# PCB_TrafficLight.net
KiCad netlist of a schematic drawn in Altium Designer
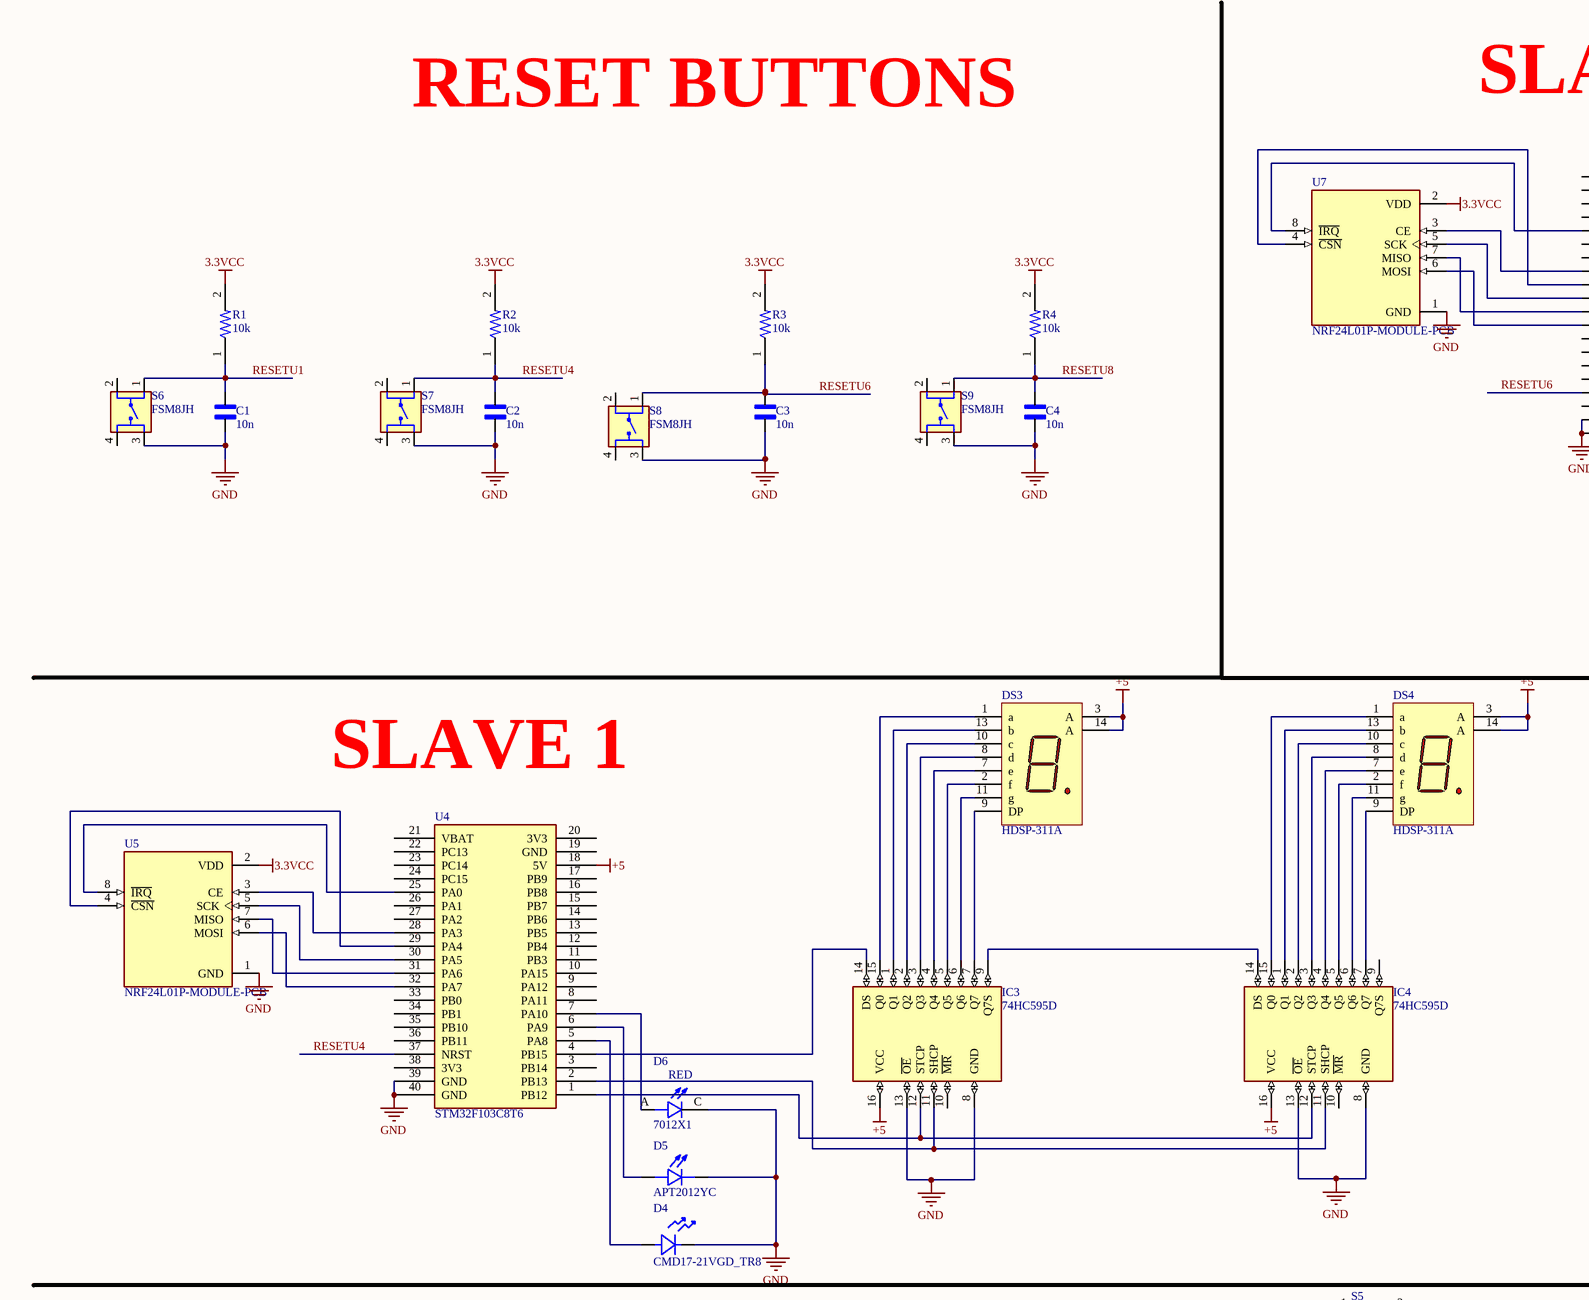
[diagram p0: PCB_TrafficLight.SchDoc, top left]
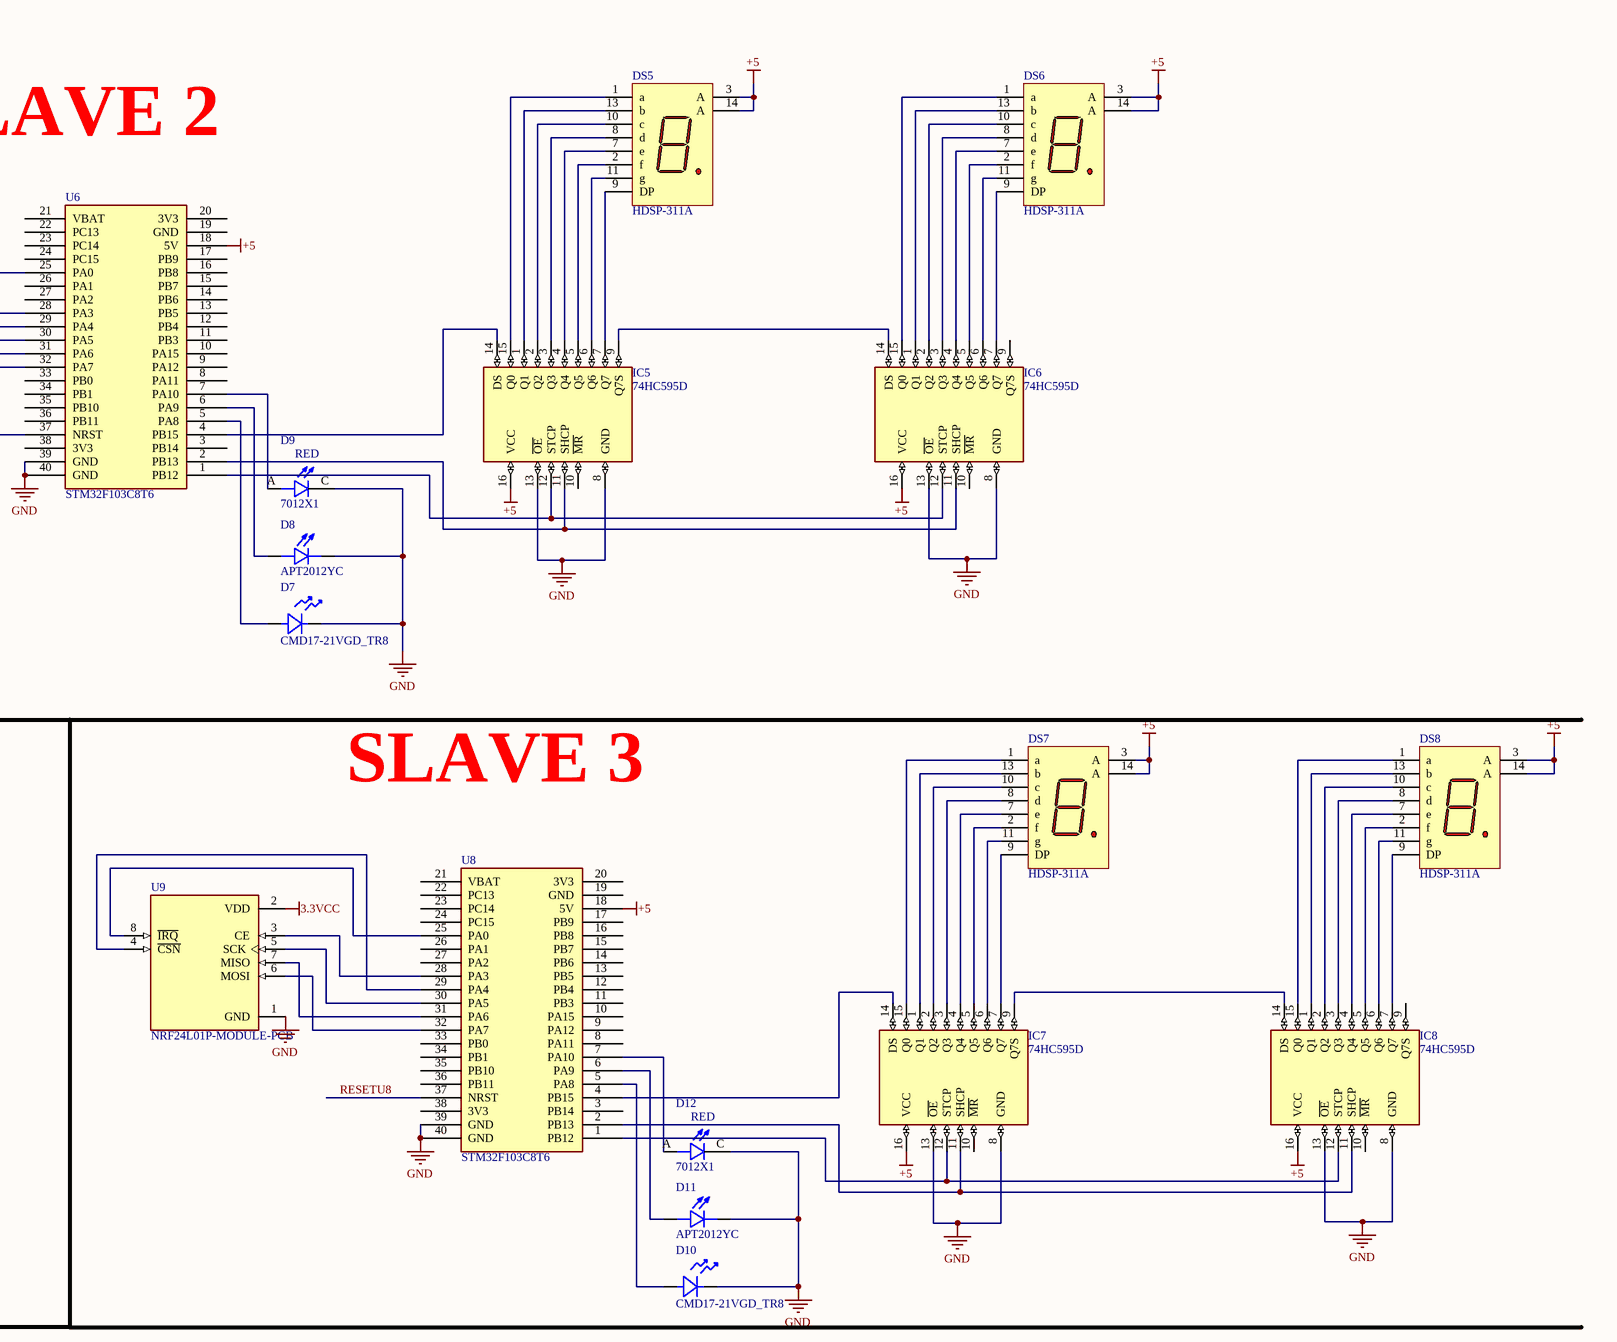
[diagram p1: PCB_TrafficLight.SchDoc, top right]
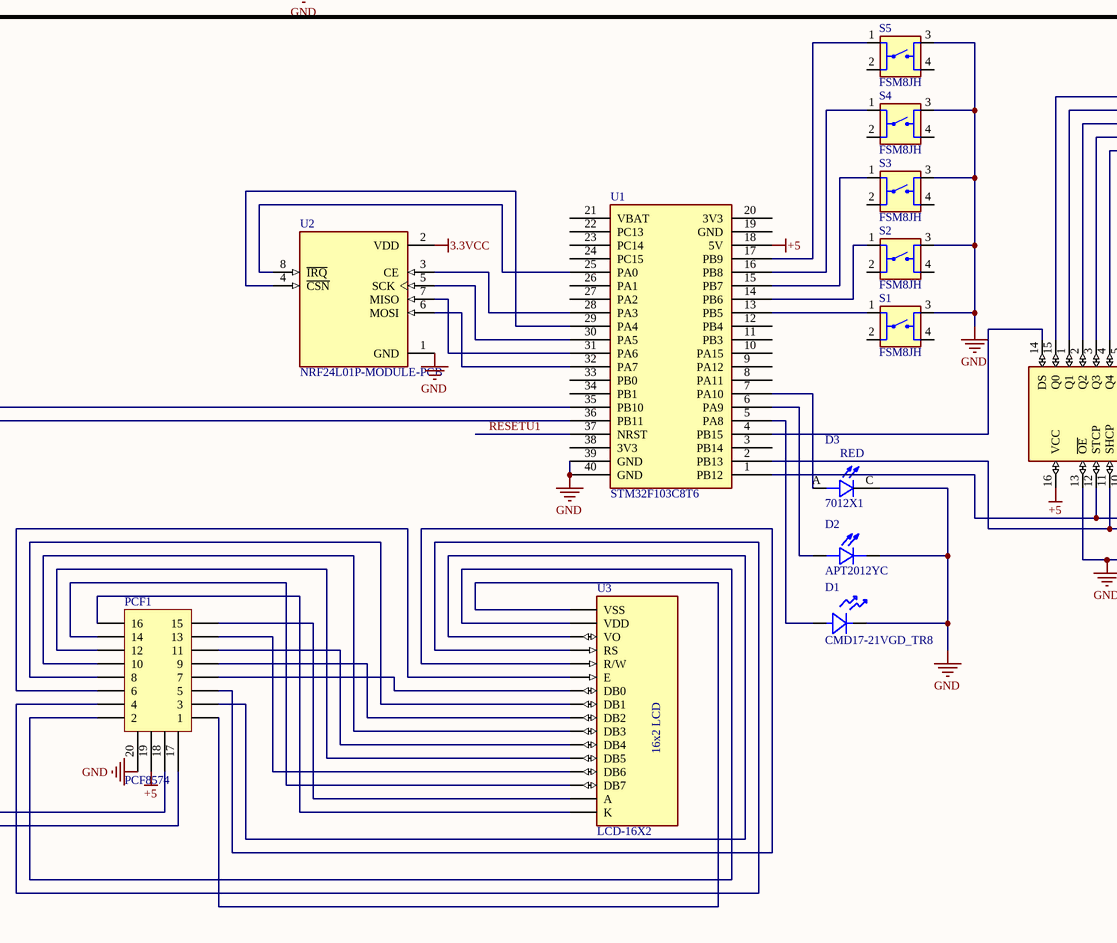
[diagram p2: PCB_TrafficLight.SchDoc, bottom left]
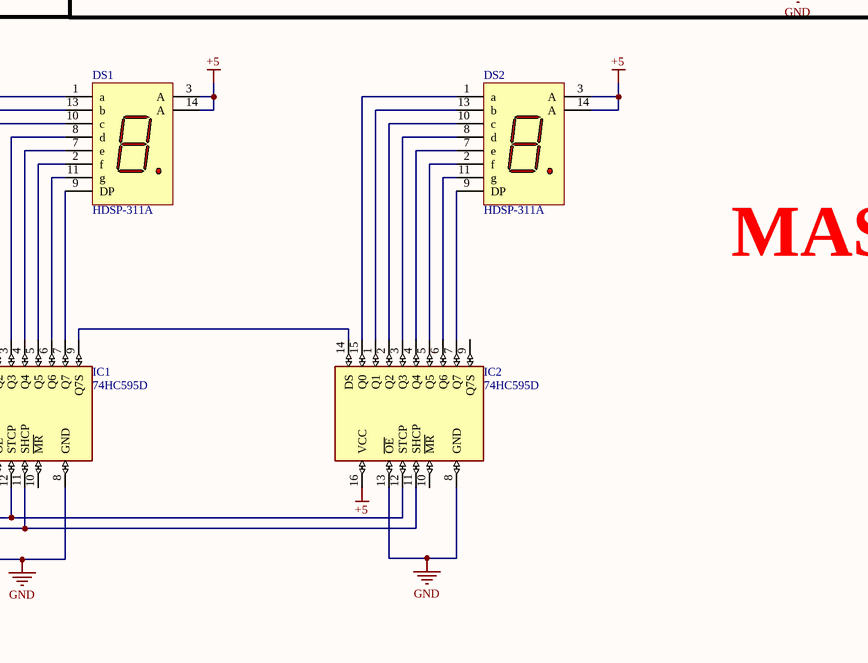
[diagram p3: PCB_TrafficLight.SchDoc, bottom right]

(export (version "E")
  (design (tool "Eeschema 10.0.6"))
  (components
    (comp (ref "C1")
      (value "10n")
      (footprint "CAPC1005X55N")
      (description "Multilayer Ceramic Capacitors MLCC - SMD/SMT")
      (fields (field (name "MF") "Murata") (field (name "MP") "GCM155R11H103KA40D"))
      (libsource (lib "GCM155R11H103KA40D") (part "GCM155R11H103KA40D"))
    )
    (comp (ref "C2")
      (value "10n")
      (footprint "CAPC1005X55N")
      (description "Multilayer Ceramic Capacitors MLCC - SMD/SMT")
      (fields (field (name "MF") "Murata") (field (name "MP") "GCM155R11H103KA40D"))
      (libsource (lib "GCM155R11H103KA40D") (part "GCM155R11H103KA40D"))
    )
    (comp (ref "C3")
      (value "10n")
      (footprint "CAPC1005X55N")
      (description "Multilayer Ceramic Capacitors MLCC - SMD/SMT")
      (fields (field (name "MF") "Murata") (field (name "MP") "GCM155R11H103KA40D"))
      (libsource (lib "GCM155R11H103KA40D") (part "GCM155R11H103KA40D"))
    )
    (comp (ref "C4")
      (value "10n")
      (footprint "CAPC1005X55N")
      (description "Multilayer Ceramic Capacitors MLCC - SMD/SMT")
      (fields (field (name "MF") "Murata") (field (name "MP") "GCM155R11H103KA40D"))
      (libsource (lib "GCM155R11H103KA40D") (part "GCM155R11H103KA40D"))
    )
    (comp (ref "D1")
      (value "CMD17-21VGD_TR8")
      (footprint "LED_CMD17-21VGD_TR8")
      (description "Green - LED Indication - Discrete 2.1V 0805 (2012 Metric)")
      (fields (field (name "MF") "VCC") (field (name "MP") "CMD17-21VGD/TR8"))
      (libsource (lib "CMD17-21VGD_TR8") (part "CMD17-21VGD_TR8"))
    )
    (comp (ref "D2")
      (value "APT2012YC")
      (footprint "LED_APT2012YC")
      (fields (field (name "MF") "{'manufacturer': u'Kingbright'}"))
      (libsource (lib "APT2012YC") (part "APT2012YC"))
    )
    (comp (ref "D3")
      (value "7012X1")
      (footprint "LED_7012X1")
      (description "Red - LED Indication - Discrete 1.7V 0805 (2012 Metric)")
      (fields (field (name "MF") "VCC"))
      (libsource (lib "7012X1") (part "7012X1"))
    )
    (comp (ref "D4")
      (value "CMD17-21VGD_TR8")
      (footprint "LED_CMD17-21VGD_TR8")
      (description "Green - LED Indication - Discrete 2.1V 0805 (2012 Metric)")
      (fields (field (name "MF") "VCC") (field (name "MP") "CMD17-21VGD/TR8"))
      (libsource (lib "CMD17-21VGD_TR8") (part "CMD17-21VGD_TR8"))
    )
    (comp (ref "D5")
      (value "APT2012YC")
      (footprint "LED_APT2012YC")
      (fields (field (name "MF") "{'manufacturer': u'Kingbright'}"))
      (libsource (lib "APT2012YC") (part "APT2012YC"))
    )
    (comp (ref "D6")
      (value "7012X1")
      (footprint "LED_7012X1")
      (description "Red - LED Indication - Discrete 1.7V 0805 (2012 Metric)")
      (fields (field (name "MF") "VCC"))
      (libsource (lib "7012X1") (part "7012X1"))
    )
    (comp (ref "D7")
      (value "CMD17-21VGD_TR8")
      (footprint "LED_CMD17-21VGD_TR8")
      (description "Green - LED Indication - Discrete 2.1V 0805 (2012 Metric)")
      (fields (field (name "MF") "VCC") (field (name "MP") "CMD17-21VGD/TR8"))
      (libsource (lib "CMD17-21VGD_TR8") (part "CMD17-21VGD_TR8"))
    )
    (comp (ref "D8")
      (value "APT2012YC")
      (footprint "LED_APT2012YC")
      (fields (field (name "MF") "{'manufacturer': u'Kingbright'}"))
      (libsource (lib "APT2012YC") (part "APT2012YC"))
    )
    (comp (ref "D9")
      (value "7012X1")
      (footprint "LED_7012X1")
      (description "Red - LED Indication - Discrete 1.7V 0805 (2012 Metric)")
      (fields (field (name "MF") "VCC"))
      (libsource (lib "7012X1") (part "7012X1"))
    )
    (comp (ref "D10")
      (value "CMD17-21VGD_TR8")
      (footprint "LED_CMD17-21VGD_TR8")
      (description "Green - LED Indication - Discrete 2.1V 0805 (2012 Metric)")
      (fields (field (name "MF") "VCC") (field (name "MP") "CMD17-21VGD/TR8"))
      (libsource (lib "CMD17-21VGD_TR8") (part "CMD17-21VGD_TR8"))
    )
    (comp (ref "D11")
      (value "APT2012YC")
      (footprint "LED_APT2012YC")
      (fields (field (name "MF") "{'manufacturer': u'Kingbright'}"))
      (libsource (lib "APT2012YC") (part "APT2012YC"))
    )
    (comp (ref "D12")
      (value "7012X1")
      (footprint "LED_7012X1")
      (description "Red - LED Indication - Discrete 1.7V 0805 (2012 Metric)")
      (fields (field (name "MF") "VCC"))
      (libsource (lib "7012X1") (part "7012X1"))
    )
    (comp (ref "DS1")
      (value "HDSP-311A")
      (footprint "F-10(14)")
      (description "10.16 mm Single Digit General Purpose AlGaAs Red 7-Segment Display: CA, RH DP")
      (fields (field (name "PUBLISHER") "Altium Limited"))
      (libsource (lib "Agilent LED Display 7-Segment, 1-Digit") (part "HDSP-311A"))
    )
    (comp (ref "DS2")
      (value "HDSP-311A")
      (footprint "F-10(14)")
      (description "10.16 mm Single Digit General Purpose AlGaAs Red 7-Segment Display: CA, RH DP")
      (fields (field (name "PUBLISHER") "Altium Limited"))
      (libsource (lib "Agilent LED Display 7-Segment, 1-Digit") (part "HDSP-311A"))
    )
    (comp (ref "DS3")
      (value "HDSP-311A")
      (footprint "F-10(14)")
      (description "10.16 mm Single Digit General Purpose AlGaAs Red 7-Segment Display: CA, RH DP")
      (fields (field (name "PUBLISHER") "Altium Limited"))
      (libsource (lib "Agilent LED Display 7-Segment, 1-Digit") (part "HDSP-311A"))
    )
    (comp (ref "DS4")
      (value "HDSP-311A")
      (footprint "F-10(14)")
      (description "10.16 mm Single Digit General Purpose AlGaAs Red 7-Segment Display: CA, RH DP")
      (fields (field (name "PUBLISHER") "Altium Limited"))
      (libsource (lib "Agilent LED Display 7-Segment, 1-Digit") (part "HDSP-311A"))
    )
    (comp (ref "DS5")
      (value "HDSP-311A")
      (footprint "F-10(14)")
      (description "10.16 mm Single Digit General Purpose AlGaAs Red 7-Segment Display: CA, RH DP")
      (fields (field (name "PUBLISHER") "Altium Limited"))
      (libsource (lib "Agilent LED Display 7-Segment, 1-Digit") (part "HDSP-311A"))
    )
    (comp (ref "DS6")
      (value "HDSP-311A")
      (footprint "F-10(14)")
      (description "10.16 mm Single Digit General Purpose AlGaAs Red 7-Segment Display: CA, RH DP")
      (fields (field (name "PUBLISHER") "Altium Limited"))
      (libsource (lib "Agilent LED Display 7-Segment, 1-Digit") (part "HDSP-311A"))
    )
    (comp (ref "DS7")
      (value "HDSP-311A")
      (footprint "F-10(14)")
      (description "10.16 mm Single Digit General Purpose AlGaAs Red 7-Segment Display: CA, RH DP")
      (fields (field (name "PUBLISHER") "Altium Limited"))
      (libsource (lib "Agilent LED Display 7-Segment, 1-Digit") (part "HDSP-311A"))
    )
    (comp (ref "DS8")
      (value "HDSP-311A")
      (footprint "F-10(14)")
      (description "10.16 mm Single Digit General Purpose AlGaAs Red 7-Segment Display: CA, RH DP")
      (fields (field (name "PUBLISHER") "Altium Limited"))
      (libsource (lib "Agilent LED Display 7-Segment, 1-Digit") (part "HDSP-311A"))
    )
    (comp (ref "IC1")
      (value "74HC595D")
      (footprint "SOIC127P600X175-16N")
      (description "Shift Register Single 8-Bit Serial to Serial/Parallel 16-Pin SOIC T/R")
      (fields (field (name "MF") "NXP Semiconductors"))
      (libsource (lib "74HC595D") (part "74HC595D"))
    )
    (comp (ref "IC2")
      (value "74HC595D")
      (footprint "SOIC127P600X175-16N")
      (description "Shift Register Single 8-Bit Serial to Serial/Parallel 16-Pin SOIC T/R")
      (fields (field (name "MF") "NXP Semiconductors"))
      (libsource (lib "74HC595D") (part "74HC595D"))
    )
    (comp (ref "IC3")
      (value "74HC595D")
      (footprint "SOIC127P600X175-16N")
      (description "Shift Register Single 8-Bit Serial to Serial/Parallel 16-Pin SOIC T/R")
      (fields (field (name "MF") "NXP Semiconductors"))
      (libsource (lib "74HC595D") (part "74HC595D"))
    )
    (comp (ref "IC4")
      (value "74HC595D")
      (footprint "SOIC127P600X175-16N")
      (description "Shift Register Single 8-Bit Serial to Serial/Parallel 16-Pin SOIC T/R")
      (fields (field (name "MF") "NXP Semiconductors"))
      (libsource (lib "74HC595D") (part "74HC595D"))
    )
    (comp (ref "IC5")
      (value "74HC595D")
      (footprint "SOIC127P600X175-16N")
      (description "Shift Register Single 8-Bit Serial to Serial/Parallel 16-Pin SOIC T/R")
      (fields (field (name "MF") "NXP Semiconductors"))
      (libsource (lib "74HC595D") (part "74HC595D"))
    )
    (comp (ref "IC6")
      (value "74HC595D")
      (footprint "SOIC127P600X175-16N")
      (description "Shift Register Single 8-Bit Serial to Serial/Parallel 16-Pin SOIC T/R")
      (fields (field (name "MF") "NXP Semiconductors"))
      (libsource (lib "74HC595D") (part "74HC595D"))
    )
    (comp (ref "IC7")
      (value "74HC595D")
      (footprint "SOIC127P600X175-16N")
      (description "Shift Register Single 8-Bit Serial to Serial/Parallel 16-Pin SOIC T/R")
      (fields (field (name "MF") "NXP Semiconductors"))
      (libsource (lib "74HC595D") (part "74HC595D"))
    )
    (comp (ref "IC8")
      (value "74HC595D")
      (footprint "SOIC127P600X175-16N")
      (description "Shift Register Single 8-Bit Serial to Serial/Parallel 16-Pin SOIC T/R")
      (fields (field (name "MF") "NXP Semiconductors"))
      (libsource (lib "74HC595D") (part "74HC595D"))
    )
    (comp (ref "PCF1") (value "PCF8574") (footprint "PCF8574") (libsource (lib "PCF8574") (part "PCF8574")))
    (comp (ref "R1")
      (value "10k")
      (footprint "RESC1608X50N_CPF0603F10KC1")
      (description "Res Thin Film 0603 10K Ohm 1% 1/16W Â±50ppm/Â°C Molded SMD SMD Paper T/R")
      (fields (field (name "TOLERANCE") "1%") (field (name "MF") "TE Connectivity"))
      (libsource (lib "CPF0603F10KC1") (part "CPF0603F10KC1"))
    )
    (comp (ref "R2")
      (value "10k")
      (footprint "RESC1608X50N_CPF0603F10KC1")
      (description "Res Thin Film 0603 10K Ohm 1% 1/16W Â±50ppm/Â°C Molded SMD SMD Paper T/R")
      (fields (field (name "TOLERANCE") "1%") (field (name "MF") "TE Connectivity"))
      (libsource (lib "CPF0603F10KC1") (part "CPF0603F10KC1"))
    )
    (comp (ref "R3")
      (value "10k")
      (footprint "RESC1608X50N_CPF0603F10KC1")
      (description "Res Thin Film 0603 10K Ohm 1% 1/16W Â±50ppm/Â°C Molded SMD SMD Paper T/R")
      (fields (field (name "TOLERANCE") "1%") (field (name "MF") "TE Connectivity"))
      (libsource (lib "CPF0603F10KC1") (part "CPF0603F10KC1"))
    )
    (comp (ref "R4")
      (value "10k")
      (footprint "RESC1608X50N_CPF0603F10KC1")
      (description "Res Thin Film 0603 10K Ohm 1% 1/16W Â±50ppm/Â°C Molded SMD SMD Paper T/R")
      (fields (field (name "TOLERANCE") "1%") (field (name "MF") "TE Connectivity"))
      (libsource (lib "CPF0603F10KC1") (part "CPF0603F10KC1"))
    )
    (comp (ref "S1")
      (value "FSM8JH")
      (footprint "SW_FSM8JH")
      (description "Tactile Switch SPST-NO Top Actuated Through Hole")
      (fields (field (name "MF") "TE Connectivity"))
      (libsource (lib "FSM8JH") (part "FSM8JH"))
    )
    (comp (ref "S2")
      (value "FSM8JH")
      (footprint "SW_FSM8JH")
      (description "Tactile Switch SPST-NO Top Actuated Through Hole")
      (fields (field (name "MF") "TE Connectivity"))
      (libsource (lib "FSM8JH") (part "FSM8JH"))
    )
    (comp (ref "S3")
      (value "FSM8JH")
      (footprint "SW_FSM8JH")
      (description "Tactile Switch SPST-NO Top Actuated Through Hole")
      (fields (field (name "MF") "TE Connectivity"))
      (libsource (lib "FSM8JH") (part "FSM8JH"))
    )
    (comp (ref "S4")
      (value "FSM8JH")
      (footprint "SW_FSM8JH")
      (description "Tactile Switch SPST-NO Top Actuated Through Hole")
      (fields (field (name "MF") "TE Connectivity"))
      (libsource (lib "FSM8JH") (part "FSM8JH"))
    )
    (comp (ref "S5")
      (value "FSM8JH")
      (footprint "SW_FSM8JH")
      (description "Tactile Switch SPST-NO Top Actuated Through Hole")
      (fields (field (name "MF") "TE Connectivity"))
      (libsource (lib "FSM8JH") (part "FSM8JH"))
    )
    (comp (ref "S6")
      (value "FSM8JH")
      (footprint "SW_FSM8JH")
      (description "Tactile Switch SPST-NO Top Actuated Through Hole")
      (fields (field (name "MF") "TE Connectivity"))
      (libsource (lib "") (part "FSM8JH_1"))
    )
    (comp (ref "S7")
      (value "FSM8JH")
      (footprint "SW_FSM8JH")
      (description "Tactile Switch SPST-NO Top Actuated Through Hole")
      (fields (field (name "MF") "TE Connectivity"))
      (libsource (lib "") (part "FSM8JH_1"))
    )
    (comp (ref "S8")
      (value "FSM8JH")
      (footprint "SW_FSM8JH")
      (description "Tactile Switch SPST-NO Top Actuated Through Hole")
      (fields (field (name "MF") "TE Connectivity"))
      (libsource (lib "") (part "FSM8JH_1"))
    )
    (comp (ref "S9")
      (value "FSM8JH")
      (footprint "SW_FSM8JH")
      (description "Tactile Switch SPST-NO Top Actuated Through Hole")
      (fields (field (name "MF") "TE Connectivity"))
      (libsource (lib "") (part "FSM8JH_1"))
    )
    (comp (ref "U1")
      (value "STM32F103C8T6")
      (footprint "Stm32 BluePill")
      (description "Designed By @Alixahedi")
      (libsource (lib "Stm32 Blue Pill") (part "BluePill"))
    )
    (comp (ref "U2")
      (value "NRF24L01P-MODULE-PCB")
      (footprint "XCVR_NRF24L01P-MODULE-PCB")
      (description "- Transceiver For Use With nRF24L01+")
      (fields (field (name "MF") "Nordic Semiconductor"))
      (libsource (lib "NRF24L01P-MODULE-PCB") (part "NRF24L01P-MODULE-PCB"))
    )
    (comp (ref "U3")
      (value "LCD-16X2")
      (footprint "MODULE_LCD-16X2")
      (description "Display Development Tools 16x2 Black on Green Char LCD w Backlight")
      (fields (field (name "MF") "Gravitech"))
      (libsource (lib "LCD-16X2") (part "LCD-16X2"))
    )
    (comp (ref "U4")
      (value "STM32F103C8T6")
      (footprint "Stm32 BluePill")
      (description "Designed By @Alixahedi")
      (libsource (lib "Stm32 Blue Pill") (part "BluePill"))
    )
    (comp (ref "U5")
      (value "NRF24L01P-MODULE-PCB")
      (footprint "XCVR_NRF24L01P-MODULE-PCB")
      (description "- Transceiver For Use With nRF24L01+")
      (fields (field (name "MF") "Nordic Semiconductor"))
      (libsource (lib "NRF24L01P-MODULE-PCB") (part "NRF24L01P-MODULE-PCB"))
    )
    (comp (ref "U6")
      (value "STM32F103C8T6")
      (footprint "Stm32 BluePill")
      (description "Designed By @Alixahedi")
      (libsource (lib "Stm32 Blue Pill") (part "BluePill"))
    )
    (comp (ref "U7")
      (value "NRF24L01P-MODULE-PCB")
      (footprint "XCVR_NRF24L01P-MODULE-PCB")
      (description "- Transceiver For Use With nRF24L01+")
      (fields (field (name "MF") "Nordic Semiconductor"))
      (libsource (lib "NRF24L01P-MODULE-PCB") (part "NRF24L01P-MODULE-PCB"))
    )
    (comp (ref "U8")
      (value "STM32F103C8T6")
      (footprint "Stm32 BluePill")
      (description "Designed By @Alixahedi")
      (libsource (lib "Stm32 Blue Pill") (part "BluePill"))
    )
    (comp (ref "U9")
      (value "NRF24L01P-MODULE-PCB")
      (footprint "XCVR_NRF24L01P-MODULE-PCB")
      (description "- Transceiver For Use With nRF24L01+")
      (fields (field (name "MF") "Nordic Semiconductor"))
      (libsource (lib "NRF24L01P-MODULE-PCB") (part "NRF24L01P-MODULE-PCB"))
    )
  )
  (nets
    (net (code "1") (name "+5") (class "Default")
      (node (ref "DS1") (pin "14") (pinfunction "A_14") (pintype "passive"))
      (node (ref "DS1") (pin "3") (pinfunction "A_3") (pintype "passive"))
      (node (ref "DS2") (pin "14") (pinfunction "A_14") (pintype "passive"))
      (node (ref "DS2") (pin "3") (pinfunction "A_3") (pintype "passive"))
      (node (ref "DS3") (pin "14") (pinfunction "A_14") (pintype "passive"))
      (node (ref "DS3") (pin "3") (pinfunction "A_3") (pintype "passive"))
      (node (ref "DS4") (pin "14") (pinfunction "A_14") (pintype "passive"))
      (node (ref "DS4") (pin "3") (pinfunction "A_3") (pintype "passive"))
      (node (ref "DS5") (pin "14") (pinfunction "A_14") (pintype "passive"))
      (node (ref "DS5") (pin "3") (pinfunction "A_3") (pintype "passive"))
      (node (ref "DS6") (pin "14") (pinfunction "A_14") (pintype "passive"))
      (node (ref "DS6") (pin "3") (pinfunction "A_3") (pintype "passive"))
      (node (ref "DS7") (pin "14") (pinfunction "A_14") (pintype "passive"))
      (node (ref "DS7") (pin "3") (pinfunction "A_3") (pintype "passive"))
      (node (ref "DS8") (pin "14") (pinfunction "A_14") (pintype "passive"))
      (node (ref "DS8") (pin "3") (pinfunction "A_3") (pintype "passive"))
      (node (ref "IC1") (pin "16") (pinfunction "VCC_16") (pintype "bidirectional"))
      (node (ref "IC2") (pin "16") (pinfunction "VCC_16") (pintype "bidirectional"))
      (node (ref "IC3") (pin "16") (pinfunction "VCC_16") (pintype "bidirectional"))
      (node (ref "IC4") (pin "16") (pinfunction "VCC_16") (pintype "bidirectional"))
      (node (ref "IC5") (pin "16") (pinfunction "VCC_16") (pintype "bidirectional"))
      (node (ref "IC6") (pin "16") (pinfunction "VCC_16") (pintype "bidirectional"))
      (node (ref "IC7") (pin "16") (pinfunction "VCC_16") (pintype "bidirectional"))
      (node (ref "IC8") (pin "16") (pinfunction "VCC_16") (pintype "bidirectional"))
      (node (ref "PCF1") (pin "19") (pinfunction "19_19") (pintype "passive"))
      (node (ref "U1") (pin "18") (pinfunction "5V_18") (pintype "passive"))
      (node (ref "U4") (pin "18") (pinfunction "5V_18") (pintype "passive"))
      (node (ref "U6") (pin "18") (pinfunction "5V_18") (pintype "passive"))
      (node (ref "U8") (pin "18") (pinfunction "5V_18") (pintype "passive"))
    )
    (net (code "2") (name "/RESETU1") (class "Default")
      (node (ref "C1") (pin "2") (pinfunction "2_2") (pintype "passive"))
      (node (ref "R1") (pin "1") (pinfunction "1_1") (pintype "passive"))
      (node (ref "S6") (pin "1") (pinfunction "1_1") (pintype "passive"))
      (node (ref "U1") (pin "37") (pinfunction "NRST_37") (pintype "passive"))
    )
    (net (code "3") (name "/RESETU4") (class "Default")
      (node (ref "C2") (pin "2") (pinfunction "2_2") (pintype "passive"))
      (node (ref "R2") (pin "1") (pinfunction "1_1") (pintype "passive"))
      (node (ref "S7") (pin "1") (pinfunction "1_1") (pintype "passive"))
      (node (ref "U4") (pin "37") (pinfunction "NRST_37") (pintype "passive"))
    )
    (net (code "4") (name "/RESETU6") (class "Default")
      (node (ref "C3") (pin "2") (pinfunction "2_2") (pintype "passive"))
      (node (ref "R3") (pin "1") (pinfunction "1_1") (pintype "passive"))
      (node (ref "S8") (pin "1") (pinfunction "1_1") (pintype "passive"))
      (node (ref "U6") (pin "37") (pinfunction "NRST_37") (pintype "passive"))
    )
    (net (code "5") (name "/RESETU8") (class "Default")
      (node (ref "C4") (pin "2") (pinfunction "2_2") (pintype "passive"))
      (node (ref "R4") (pin "1") (pinfunction "1_1") (pintype "passive"))
      (node (ref "S9") (pin "1") (pinfunction "1_1") (pintype "passive"))
      (node (ref "U8") (pin "37") (pinfunction "NRST_37") (pintype "passive"))
    )
    (net (code "6") (name "3.3VCC") (class "Default")
      (node (ref "R1") (pin "2") (pinfunction "2_2") (pintype "passive"))
      (node (ref "R2") (pin "2") (pinfunction "2_2") (pintype "passive"))
      (node (ref "R3") (pin "2") (pinfunction "2_2") (pintype "passive"))
      (node (ref "R4") (pin "2") (pinfunction "2_2") (pintype "passive"))
      (node (ref "U2") (pin "2") (pinfunction "VDD_2") (pintype "power_in"))
      (node (ref "U5") (pin "2") (pinfunction "VDD_2") (pintype "power_in"))
      (node (ref "U7") (pin "2") (pinfunction "VDD_2") (pintype "power_in"))
      (node (ref "U9") (pin "2") (pinfunction "VDD_2") (pintype "power_in"))
    )
    (net (code "7") (name "GND") (class "Default")
      (node (ref "C1") (pin "1") (pinfunction "1_1") (pintype "passive"))
      (node (ref "C2") (pin "1") (pinfunction "1_1") (pintype "passive"))
      (node (ref "C3") (pin "1") (pinfunction "1_1") (pintype "passive"))
      (node (ref "C4") (pin "1") (pinfunction "1_1") (pintype "passive"))
      (node (ref "D1") (pin "2") (pinfunction "2_2") (pintype "passive"))
      (node (ref "D10") (pin "2") (pinfunction "2_2") (pintype "passive"))
      (node (ref "D11") (pin "1") (pinfunction "C_1") (pintype "passive"))
      (node (ref "D12") (pin "C") (pinfunction "C_C") (pintype "passive"))
      (node (ref "D2") (pin "1") (pinfunction "C_1") (pintype "passive"))
      (node (ref "D3") (pin "C") (pinfunction "C_C") (pintype "passive"))
      (node (ref "D4") (pin "2") (pinfunction "2_2") (pintype "passive"))
      (node (ref "D5") (pin "1") (pinfunction "C_1") (pintype "passive"))
      (node (ref "D6") (pin "C") (pinfunction "C_C") (pintype "passive"))
      (node (ref "D7") (pin "2") (pinfunction "2_2") (pintype "passive"))
      (node (ref "D8") (pin "1") (pinfunction "C_1") (pintype "passive"))
      (node (ref "D9") (pin "C") (pinfunction "C_C") (pintype "passive"))
      (node (ref "IC1") (pin "13") (pinfunction "~{OE}_13") (pintype "bidirectional"))
      (node (ref "IC1") (pin "8") (pinfunction "GND_8") (pintype "bidirectional"))
      (node (ref "IC2") (pin "13") (pinfunction "~{OE}_13") (pintype "bidirectional"))
      (node (ref "IC2") (pin "8") (pinfunction "GND_8") (pintype "bidirectional"))
      (node (ref "IC3") (pin "13") (pinfunction "~{OE}_13") (pintype "bidirectional"))
      (node (ref "IC3") (pin "8") (pinfunction "GND_8") (pintype "bidirectional"))
      (node (ref "IC4") (pin "13") (pinfunction "~{OE}_13") (pintype "bidirectional"))
      (node (ref "IC4") (pin "8") (pinfunction "GND_8") (pintype "bidirectional"))
      (node (ref "IC5") (pin "13") (pinfunction "~{OE}_13") (pintype "bidirectional"))
      (node (ref "IC5") (pin "8") (pinfunction "GND_8") (pintype "bidirectional"))
      (node (ref "IC6") (pin "13") (pinfunction "~{OE}_13") (pintype "bidirectional"))
      (node (ref "IC6") (pin "8") (pinfunction "GND_8") (pintype "bidirectional"))
      (node (ref "IC7") (pin "13") (pinfunction "~{OE}_13") (pintype "bidirectional"))
      (node (ref "IC7") (pin "8") (pinfunction "GND_8") (pintype "bidirectional"))
      (node (ref "IC8") (pin "13") (pinfunction "~{OE}_13") (pintype "bidirectional"))
      (node (ref "IC8") (pin "8") (pinfunction "GND_8") (pintype "bidirectional"))
      (node (ref "PCF1") (pin "20") (pinfunction "20_20") (pintype "passive"))
      (node (ref "S1") (pin "3") (pinfunction "3_3") (pintype "passive"))
      (node (ref "S2") (pin "3") (pinfunction "3_3") (pintype "passive"))
      (node (ref "S3") (pin "3") (pinfunction "3_3") (pintype "passive"))
      (node (ref "S4") (pin "3") (pinfunction "3_3") (pintype "passive"))
      (node (ref "S5") (pin "3") (pinfunction "3_3") (pintype "passive"))
      (node (ref "S6") (pin "3") (pinfunction "3_3") (pintype "passive"))
      (node (ref "S7") (pin "3") (pinfunction "3_3") (pintype "passive"))
      (node (ref "S8") (pin "3") (pinfunction "3_3") (pintype "passive"))
      (node (ref "S9") (pin "3") (pinfunction "3_3") (pintype "passive"))
      (node (ref "U1") (pin "39") (pinfunction "GND_39") (pintype "passive"))
      (node (ref "U1") (pin "40") (pinfunction "GND_40") (pintype "passive"))
      (node (ref "U2") (pin "1") (pinfunction "GND_1") (pintype "power_in"))
      (node (ref "U4") (pin "39") (pinfunction "GND_39") (pintype "passive"))
      (node (ref "U4") (pin "40") (pinfunction "GND_40") (pintype "passive"))
      (node (ref "U5") (pin "1") (pinfunction "GND_1") (pintype "power_in"))
      (node (ref "U6") (pin "39") (pinfunction "GND_39") (pintype "passive"))
      (node (ref "U6") (pin "40") (pinfunction "GND_40") (pintype "passive"))
      (node (ref "U7") (pin "1") (pinfunction "GND_1") (pintype "power_in"))
      (node (ref "U8") (pin "39") (pinfunction "GND_39") (pintype "passive"))
      (node (ref "U8") (pin "40") (pinfunction "GND_40") (pintype "passive"))
      (node (ref "U9") (pin "1") (pinfunction "GND_1") (pintype "power_in"))
    )
    (net (code "8") (name "Net-(D2-A)") (class "Default")
      (node (ref "D2") (pin "2") (pinfunction "A_2") (pintype "passive"))
      (node (ref "U1") (pin "6") (pinfunction "PA9_6") (pintype "passive"))
    )
    (net (code "9") (name "Net-(D5-A)") (class "Default")
      (node (ref "D5") (pin "2") (pinfunction "A_2") (pintype "passive"))
      (node (ref "U4") (pin "6") (pinfunction "PA9_6") (pintype "passive"))
    )
    (net (code "10") (name "Net-(D8-A)") (class "Default")
      (node (ref "D8") (pin "2") (pinfunction "A_2") (pintype "passive"))
      (node (ref "U6") (pin "6") (pinfunction "PA9_6") (pintype "passive"))
    )
    (net (code "11") (name "Net-(D11-A)") (class "Default")
      (node (ref "D11") (pin "2") (pinfunction "A_2") (pintype "passive"))
      (node (ref "U8") (pin "6") (pinfunction "PA9_6") (pintype "passive"))
    )
    (net (code "12") (name "Net-(DS1-DP)") (class "Default")
      (node (ref "DS1") (pin "9") (pinfunction "DP_9") (pintype "passive"))
      (node (ref "IC1") (pin "7") (pinfunction "Q7_7") (pintype "bidirectional"))
    )
    (net (code "13") (name "Net-(DS1-a)") (class "Default")
      (node (ref "DS1") (pin "1") (pinfunction "a_1") (pintype "passive"))
      (node (ref "IC1") (pin "15") (pinfunction "Q0_15") (pintype "bidirectional"))
    )
    (net (code "14") (name "Net-(DS1-b)") (class "Default")
      (node (ref "DS1") (pin "13") (pinfunction "b_13") (pintype "passive"))
      (node (ref "IC1") (pin "1") (pinfunction "Q1_1") (pintype "bidirectional"))
    )
    (net (code "15") (name "Net-(DS1-c)") (class "Default")
      (node (ref "DS1") (pin "10") (pinfunction "c_10") (pintype "passive"))
      (node (ref "IC1") (pin "2") (pinfunction "Q2_2") (pintype "bidirectional"))
    )
    (net (code "16") (name "Net-(DS1-d)") (class "Default")
      (node (ref "DS1") (pin "8") (pinfunction "d_8") (pintype "passive"))
      (node (ref "IC1") (pin "3") (pinfunction "Q3_3") (pintype "bidirectional"))
    )
    (net (code "17") (name "Net-(DS1-e)") (class "Default")
      (node (ref "DS1") (pin "7") (pinfunction "e_7") (pintype "passive"))
      (node (ref "IC1") (pin "4") (pinfunction "Q4_4") (pintype "bidirectional"))
    )
    (net (code "18") (name "Net-(DS1-f)") (class "Default")
      (node (ref "DS1") (pin "2") (pinfunction "f_2") (pintype "passive"))
      (node (ref "IC1") (pin "5") (pinfunction "Q5_5") (pintype "bidirectional"))
    )
    (net (code "19") (name "Net-(DS1-g)") (class "Default")
      (node (ref "DS1") (pin "11") (pinfunction "g_11") (pintype "passive"))
      (node (ref "IC1") (pin "6") (pinfunction "Q6_6") (pintype "bidirectional"))
    )
    (net (code "20") (name "Net-(DS2-DP)") (class "Default")
      (node (ref "DS2") (pin "9") (pinfunction "DP_9") (pintype "passive"))
      (node (ref "IC2") (pin "7") (pinfunction "Q7_7") (pintype "bidirectional"))
    )
    (net (code "21") (name "Net-(DS2-a)") (class "Default")
      (node (ref "DS2") (pin "1") (pinfunction "a_1") (pintype "passive"))
      (node (ref "IC2") (pin "15") (pinfunction "Q0_15") (pintype "bidirectional"))
    )
    (net (code "22") (name "Net-(DS2-b)") (class "Default")
      (node (ref "DS2") (pin "13") (pinfunction "b_13") (pintype "passive"))
      (node (ref "IC2") (pin "1") (pinfunction "Q1_1") (pintype "bidirectional"))
    )
    (net (code "23") (name "Net-(DS2-c)") (class "Default")
      (node (ref "DS2") (pin "10") (pinfunction "c_10") (pintype "passive"))
      (node (ref "IC2") (pin "2") (pinfunction "Q2_2") (pintype "bidirectional"))
    )
    (net (code "24") (name "Net-(DS2-d)") (class "Default")
      (node (ref "DS2") (pin "8") (pinfunction "d_8") (pintype "passive"))
      (node (ref "IC2") (pin "3") (pinfunction "Q3_3") (pintype "bidirectional"))
    )
    (net (code "25") (name "Net-(DS2-e)") (class "Default")
      (node (ref "DS2") (pin "7") (pinfunction "e_7") (pintype "passive"))
      (node (ref "IC2") (pin "4") (pinfunction "Q4_4") (pintype "bidirectional"))
    )
    (net (code "26") (name "Net-(DS2-f)") (class "Default")
      (node (ref "DS2") (pin "2") (pinfunction "f_2") (pintype "passive"))
      (node (ref "IC2") (pin "5") (pinfunction "Q5_5") (pintype "bidirectional"))
    )
    (net (code "27") (name "Net-(DS2-g)") (class "Default")
      (node (ref "DS2") (pin "11") (pinfunction "g_11") (pintype "passive"))
      (node (ref "IC2") (pin "6") (pinfunction "Q6_6") (pintype "bidirectional"))
    )
    (net (code "28") (name "Net-(DS3-DP)") (class "Default")
      (node (ref "DS3") (pin "9") (pinfunction "DP_9") (pintype "passive"))
      (node (ref "IC3") (pin "7") (pinfunction "Q7_7") (pintype "bidirectional"))
    )
    (net (code "29") (name "Net-(DS3-a)") (class "Default")
      (node (ref "DS3") (pin "1") (pinfunction "a_1") (pintype "passive"))
      (node (ref "IC3") (pin "15") (pinfunction "Q0_15") (pintype "bidirectional"))
    )
    (net (code "30") (name "Net-(DS3-b)") (class "Default")
      (node (ref "DS3") (pin "13") (pinfunction "b_13") (pintype "passive"))
      (node (ref "IC3") (pin "1") (pinfunction "Q1_1") (pintype "bidirectional"))
    )
    (net (code "31") (name "Net-(DS3-c)") (class "Default")
      (node (ref "DS3") (pin "10") (pinfunction "c_10") (pintype "passive"))
      (node (ref "IC3") (pin "2") (pinfunction "Q2_2") (pintype "bidirectional"))
    )
    (net (code "32") (name "Net-(DS3-d)") (class "Default")
      (node (ref "DS3") (pin "8") (pinfunction "d_8") (pintype "passive"))
      (node (ref "IC3") (pin "3") (pinfunction "Q3_3") (pintype "bidirectional"))
    )
    (net (code "33") (name "Net-(DS3-e)") (class "Default")
      (node (ref "DS3") (pin "7") (pinfunction "e_7") (pintype "passive"))
      (node (ref "IC3") (pin "4") (pinfunction "Q4_4") (pintype "bidirectional"))
    )
    (net (code "34") (name "Net-(DS3-f)") (class "Default")
      (node (ref "DS3") (pin "2") (pinfunction "f_2") (pintype "passive"))
      (node (ref "IC3") (pin "5") (pinfunction "Q5_5") (pintype "bidirectional"))
    )
    (net (code "35") (name "Net-(DS3-g)") (class "Default")
      (node (ref "DS3") (pin "11") (pinfunction "g_11") (pintype "passive"))
      (node (ref "IC3") (pin "6") (pinfunction "Q6_6") (pintype "bidirectional"))
    )
    (net (code "36") (name "Net-(DS4-DP)") (class "Default")
      (node (ref "DS4") (pin "9") (pinfunction "DP_9") (pintype "passive"))
      (node (ref "IC4") (pin "7") (pinfunction "Q7_7") (pintype "bidirectional"))
    )
    (net (code "37") (name "Net-(DS4-a)") (class "Default")
      (node (ref "DS4") (pin "1") (pinfunction "a_1") (pintype "passive"))
      (node (ref "IC4") (pin "15") (pinfunction "Q0_15") (pintype "bidirectional"))
    )
    (net (code "38") (name "Net-(DS4-b)") (class "Default")
      (node (ref "DS4") (pin "13") (pinfunction "b_13") (pintype "passive"))
      (node (ref "IC4") (pin "1") (pinfunction "Q1_1") (pintype "bidirectional"))
    )
    (net (code "39") (name "Net-(DS4-c)") (class "Default")
      (node (ref "DS4") (pin "10") (pinfunction "c_10") (pintype "passive"))
      (node (ref "IC4") (pin "2") (pinfunction "Q2_2") (pintype "bidirectional"))
    )
    (net (code "40") (name "Net-(DS4-d)") (class "Default")
      (node (ref "DS4") (pin "8") (pinfunction "d_8") (pintype "passive"))
      (node (ref "IC4") (pin "3") (pinfunction "Q3_3") (pintype "bidirectional"))
    )
    (net (code "41") (name "Net-(DS4-e)") (class "Default")
      (node (ref "DS4") (pin "7") (pinfunction "e_7") (pintype "passive"))
      (node (ref "IC4") (pin "4") (pinfunction "Q4_4") (pintype "bidirectional"))
    )
    (net (code "42") (name "Net-(DS4-f)") (class "Default")
      (node (ref "DS4") (pin "2") (pinfunction "f_2") (pintype "passive"))
      (node (ref "IC4") (pin "5") (pinfunction "Q5_5") (pintype "bidirectional"))
    )
    (net (code "43") (name "Net-(DS4-g)") (class "Default")
      (node (ref "DS4") (pin "11") (pinfunction "g_11") (pintype "passive"))
      (node (ref "IC4") (pin "6") (pinfunction "Q6_6") (pintype "bidirectional"))
    )
    (net (code "44") (name "Net-(DS5-DP)") (class "Default")
      (node (ref "DS5") (pin "9") (pinfunction "DP_9") (pintype "passive"))
      (node (ref "IC5") (pin "7") (pinfunction "Q7_7") (pintype "bidirectional"))
    )
    (net (code "45") (name "Net-(DS5-a)") (class "Default")
      (node (ref "DS5") (pin "1") (pinfunction "a_1") (pintype "passive"))
      (node (ref "IC5") (pin "15") (pinfunction "Q0_15") (pintype "bidirectional"))
    )
    (net (code "46") (name "Net-(DS5-b)") (class "Default")
      (node (ref "DS5") (pin "13") (pinfunction "b_13") (pintype "passive"))
      (node (ref "IC5") (pin "1") (pinfunction "Q1_1") (pintype "bidirectional"))
    )
    (net (code "47") (name "Net-(DS5-c)") (class "Default")
      (node (ref "DS5") (pin "10") (pinfunction "c_10") (pintype "passive"))
      (node (ref "IC5") (pin "2") (pinfunction "Q2_2") (pintype "bidirectional"))
    )
    (net (code "48") (name "Net-(DS5-d)") (class "Default")
      (node (ref "DS5") (pin "8") (pinfunction "d_8") (pintype "passive"))
      (node (ref "IC5") (pin "3") (pinfunction "Q3_3") (pintype "bidirectional"))
    )
    (net (code "49") (name "Net-(DS5-e)") (class "Default")
      (node (ref "DS5") (pin "7") (pinfunction "e_7") (pintype "passive"))
      (node (ref "IC5") (pin "4") (pinfunction "Q4_4") (pintype "bidirectional"))
    )
    (net (code "50") (name "Net-(DS5-f)") (class "Default")
      (node (ref "DS5") (pin "2") (pinfunction "f_2") (pintype "passive"))
      (node (ref "IC5") (pin "5") (pinfunction "Q5_5") (pintype "bidirectional"))
    )
    (net (code "51") (name "Net-(DS5-g)") (class "Default")
      (node (ref "DS5") (pin "11") (pinfunction "g_11") (pintype "passive"))
      (node (ref "IC5") (pin "6") (pinfunction "Q6_6") (pintype "bidirectional"))
    )
    (net (code "52") (name "Net-(DS6-DP)") (class "Default")
      (node (ref "DS6") (pin "9") (pinfunction "DP_9") (pintype "passive"))
      (node (ref "IC6") (pin "7") (pinfunction "Q7_7") (pintype "bidirectional"))
    )
    (net (code "53") (name "Net-(DS6-a)") (class "Default")
      (node (ref "DS6") (pin "1") (pinfunction "a_1") (pintype "passive"))
      (node (ref "IC6") (pin "15") (pinfunction "Q0_15") (pintype "bidirectional"))
    )
    (net (code "54") (name "Net-(DS6-b)") (class "Default")
      (node (ref "DS6") (pin "13") (pinfunction "b_13") (pintype "passive"))
      (node (ref "IC6") (pin "1") (pinfunction "Q1_1") (pintype "bidirectional"))
    )
    (net (code "55") (name "Net-(DS6-c)") (class "Default")
      (node (ref "DS6") (pin "10") (pinfunction "c_10") (pintype "passive"))
      (node (ref "IC6") (pin "2") (pinfunction "Q2_2") (pintype "bidirectional"))
    )
    (net (code "56") (name "Net-(DS6-d)") (class "Default")
      (node (ref "DS6") (pin "8") (pinfunction "d_8") (pintype "passive"))
      (node (ref "IC6") (pin "3") (pinfunction "Q3_3") (pintype "bidirectional"))
    )
    (net (code "57") (name "Net-(DS6-e)") (class "Default")
      (node (ref "DS6") (pin "7") (pinfunction "e_7") (pintype "passive"))
      (node (ref "IC6") (pin "4") (pinfunction "Q4_4") (pintype "bidirectional"))
    )
    (net (code "58") (name "Net-(DS6-f)") (class "Default")
      (node (ref "DS6") (pin "2") (pinfunction "f_2") (pintype "passive"))
      (node (ref "IC6") (pin "5") (pinfunction "Q5_5") (pintype "bidirectional"))
    )
    (net (code "59") (name "Net-(DS6-g)") (class "Default")
      (node (ref "DS6") (pin "11") (pinfunction "g_11") (pintype "passive"))
      (node (ref "IC6") (pin "6") (pinfunction "Q6_6") (pintype "bidirectional"))
    )
    (net (code "60") (name "Net-(DS7-DP)") (class "Default")
      (node (ref "DS7") (pin "9") (pinfunction "DP_9") (pintype "passive"))
      (node (ref "IC7") (pin "7") (pinfunction "Q7_7") (pintype "bidirectional"))
    )
    (net (code "61") (name "Net-(DS7-a)") (class "Default")
      (node (ref "DS7") (pin "1") (pinfunction "a_1") (pintype "passive"))
      (node (ref "IC7") (pin "15") (pinfunction "Q0_15") (pintype "bidirectional"))
    )
    (net (code "62") (name "Net-(DS7-b)") (class "Default")
      (node (ref "DS7") (pin "13") (pinfunction "b_13") (pintype "passive"))
      (node (ref "IC7") (pin "1") (pinfunction "Q1_1") (pintype "bidirectional"))
    )
    (net (code "63") (name "Net-(DS7-c)") (class "Default")
      (node (ref "DS7") (pin "10") (pinfunction "c_10") (pintype "passive"))
      (node (ref "IC7") (pin "2") (pinfunction "Q2_2") (pintype "bidirectional"))
    )
    (net (code "64") (name "Net-(DS7-d)") (class "Default")
      (node (ref "DS7") (pin "8") (pinfunction "d_8") (pintype "passive"))
      (node (ref "IC7") (pin "3") (pinfunction "Q3_3") (pintype "bidirectional"))
    )
    (net (code "65") (name "Net-(DS7-e)") (class "Default")
      (node (ref "DS7") (pin "7") (pinfunction "e_7") (pintype "passive"))
      (node (ref "IC7") (pin "4") (pinfunction "Q4_4") (pintype "bidirectional"))
    )
    (net (code "66") (name "Net-(DS7-f)") (class "Default")
      (node (ref "DS7") (pin "2") (pinfunction "f_2") (pintype "passive"))
      (node (ref "IC7") (pin "5") (pinfunction "Q5_5") (pintype "bidirectional"))
    )
    (net (code "67") (name "Net-(DS7-g)") (class "Default")
      (node (ref "DS7") (pin "11") (pinfunction "g_11") (pintype "passive"))
      (node (ref "IC7") (pin "6") (pinfunction "Q6_6") (pintype "bidirectional"))
    )
    (net (code "68") (name "Net-(DS8-DP)") (class "Default")
      (node (ref "DS8") (pin "9") (pinfunction "DP_9") (pintype "passive"))
      (node (ref "IC8") (pin "7") (pinfunction "Q7_7") (pintype "bidirectional"))
    )
    (net (code "69") (name "Net-(DS8-a)") (class "Default")
      (node (ref "DS8") (pin "1") (pinfunction "a_1") (pintype "passive"))
      (node (ref "IC8") (pin "15") (pinfunction "Q0_15") (pintype "bidirectional"))
    )
    (net (code "70") (name "Net-(DS8-b)") (class "Default")
      (node (ref "DS8") (pin "13") (pinfunction "b_13") (pintype "passive"))
      (node (ref "IC8") (pin "1") (pinfunction "Q1_1") (pintype "bidirectional"))
    )
    (net (code "71") (name "Net-(DS8-c)") (class "Default")
      (node (ref "DS8") (pin "10") (pinfunction "c_10") (pintype "passive"))
      (node (ref "IC8") (pin "2") (pinfunction "Q2_2") (pintype "bidirectional"))
    )
    (net (code "72") (name "Net-(DS8-d)") (class "Default")
      (node (ref "DS8") (pin "8") (pinfunction "d_8") (pintype "passive"))
      (node (ref "IC8") (pin "3") (pinfunction "Q3_3") (pintype "bidirectional"))
    )
    (net (code "73") (name "Net-(DS8-e)") (class "Default")
      (node (ref "DS8") (pin "7") (pinfunction "e_7") (pintype "passive"))
      (node (ref "IC8") (pin "4") (pinfunction "Q4_4") (pintype "bidirectional"))
    )
    (net (code "74") (name "Net-(DS8-f)") (class "Default")
      (node (ref "DS8") (pin "2") (pinfunction "f_2") (pintype "passive"))
      (node (ref "IC8") (pin "5") (pinfunction "Q5_5") (pintype "bidirectional"))
    )
    (net (code "75") (name "Net-(DS8-g)") (class "Default")
      (node (ref "DS8") (pin "11") (pinfunction "g_11") (pintype "passive"))
      (node (ref "IC8") (pin "6") (pinfunction "Q6_6") (pintype "bidirectional"))
    )
    (net (code "76") (name "Net-(IC1-DS)") (class "Default")
      (node (ref "IC1") (pin "14") (pinfunction "DS_14") (pintype "bidirectional"))
      (node (ref "U1") (pin "4") (pinfunction "PB15_4") (pintype "passive"))
    )
    (net (code "77") (name "Net-(IC1-Q7S)") (class "Default")
      (node (ref "IC1") (pin "9") (pinfunction "Q7S_9") (pintype "bidirectional"))
      (node (ref "IC2") (pin "14") (pinfunction "DS_14") (pintype "bidirectional"))
    )
    (net (code "78") (name "Net-(IC1-SHCP)") (class "Default")
      (node (ref "IC1") (pin "11") (pinfunction "SHCP_11") (pintype "bidirectional"))
      (node (ref "IC2") (pin "11") (pinfunction "SHCP_11") (pintype "bidirectional"))
      (node (ref "U1") (pin "2") (pinfunction "PB13_2") (pintype "passive"))
    )
    (net (code "79") (name "Net-(IC1-STCP)") (class "Default")
      (node (ref "IC1") (pin "12") (pinfunction "STCP_12") (pintype "bidirectional"))
      (node (ref "IC2") (pin "12") (pinfunction "STCP_12") (pintype "bidirectional"))
      (node (ref "U1") (pin "1") (pinfunction "PB12_1") (pintype "passive"))
    )
    (net (code "80") (name "Net-(IC3-DS)") (class "Default")
      (node (ref "IC3") (pin "14") (pinfunction "DS_14") (pintype "bidirectional"))
      (node (ref "U4") (pin "4") (pinfunction "PB15_4") (pintype "passive"))
    )
    (net (code "81") (name "Net-(IC3-Q7S)") (class "Default")
      (node (ref "IC3") (pin "9") (pinfunction "Q7S_9") (pintype "bidirectional"))
      (node (ref "IC4") (pin "14") (pinfunction "DS_14") (pintype "bidirectional"))
    )
    (net (code "82") (name "Net-(IC3-SHCP)") (class "Default")
      (node (ref "IC3") (pin "11") (pinfunction "SHCP_11") (pintype "bidirectional"))
      (node (ref "IC4") (pin "11") (pinfunction "SHCP_11") (pintype "bidirectional"))
      (node (ref "U4") (pin "2") (pinfunction "PB13_2") (pintype "passive"))
    )
    (net (code "83") (name "Net-(IC3-STCP)") (class "Default")
      (node (ref "IC3") (pin "12") (pinfunction "STCP_12") (pintype "bidirectional"))
      (node (ref "IC4") (pin "12") (pinfunction "STCP_12") (pintype "bidirectional"))
      (node (ref "U4") (pin "1") (pinfunction "PB12_1") (pintype "passive"))
    )
    (net (code "84") (name "Net-(IC5-DS)") (class "Default")
      (node (ref "IC5") (pin "14") (pinfunction "DS_14") (pintype "bidirectional"))
      (node (ref "U6") (pin "4") (pinfunction "PB15_4") (pintype "passive"))
    )
    (net (code "85") (name "Net-(IC5-Q7S)") (class "Default")
      (node (ref "IC5") (pin "9") (pinfunction "Q7S_9") (pintype "bidirectional"))
      (node (ref "IC6") (pin "14") (pinfunction "DS_14") (pintype "bidirectional"))
    )
    (net (code "86") (name "Net-(IC5-SHCP)") (class "Default")
      (node (ref "IC5") (pin "11") (pinfunction "SHCP_11") (pintype "bidirectional"))
      (node (ref "IC6") (pin "11") (pinfunction "SHCP_11") (pintype "bidirectional"))
      (node (ref "U6") (pin "2") (pinfunction "PB13_2") (pintype "passive"))
    )
    (net (code "87") (name "Net-(IC5-STCP)") (class "Default")
      (node (ref "IC5") (pin "12") (pinfunction "STCP_12") (pintype "bidirectional"))
      (node (ref "IC6") (pin "12") (pinfunction "STCP_12") (pintype "bidirectional"))
      (node (ref "U6") (pin "1") (pinfunction "PB12_1") (pintype "passive"))
    )
    (net (code "88") (name "Net-(IC7-DS)") (class "Default")
      (node (ref "IC7") (pin "14") (pinfunction "DS_14") (pintype "bidirectional"))
      (node (ref "U8") (pin "4") (pinfunction "PB15_4") (pintype "passive"))
    )
    (net (code "89") (name "Net-(IC7-Q7S)") (class "Default")
      (node (ref "IC7") (pin "9") (pinfunction "Q7S_9") (pintype "bidirectional"))
      (node (ref "IC8") (pin "14") (pinfunction "DS_14") (pintype "bidirectional"))
    )
    (net (code "90") (name "Net-(IC7-SHCP)") (class "Default")
      (node (ref "IC7") (pin "11") (pinfunction "SHCP_11") (pintype "bidirectional"))
      (node (ref "IC8") (pin "11") (pinfunction "SHCP_11") (pintype "bidirectional"))
      (node (ref "U8") (pin "2") (pinfunction "PB13_2") (pintype "passive"))
    )
    (net (code "91") (name "Net-(IC7-STCP)") (class "Default")
      (node (ref "IC7") (pin "12") (pinfunction "STCP_12") (pintype "bidirectional"))
      (node (ref "IC8") (pin "12") (pinfunction "STCP_12") (pintype "bidirectional"))
      (node (ref "U8") (pin "1") (pinfunction "PB12_1") (pintype "passive"))
    )
    (net (code "92") (name "Net-(U1-PA0)") (class "Default")
      (node (ref "U1") (pin "25") (pinfunction "PA0_25") (pintype "passive"))
      (node (ref "U2") (pin "8") (pinfunction "~{IRQ}_8") (pintype "input"))
    )
    (net (code "93") (name "Net-(U1-PA3)") (class "Default")
      (node (ref "U1") (pin "28") (pinfunction "PA3_28") (pintype "passive"))
      (node (ref "U2") (pin "3") (pinfunction "CE_3") (pintype "input"))
    )
    (net (code "94") (name "Net-(U1-PA4)") (class "Default")
      (node (ref "U1") (pin "29") (pinfunction "PA4_29") (pintype "passive"))
      (node (ref "U2") (pin "4") (pinfunction "~{CSN}_4") (pintype "input"))
    )
    (net (code "95") (name "Net-(U1-PA5)") (class "Default")
      (node (ref "U1") (pin "30") (pinfunction "PA5_30") (pintype "passive"))
      (node (ref "U2") (pin "5") (pinfunction "SCK_5") (pintype "input"))
    )
    (net (code "96") (name "Net-(U1-PA6)") (class "Default")
      (node (ref "U1") (pin "31") (pinfunction "PA6_31") (pintype "passive"))
      (node (ref "U2") (pin "7") (pinfunction "MISO_7") (pintype "input"))
    )
    (net (code "97") (name "Net-(U1-PA7)") (class "Default")
      (node (ref "U1") (pin "32") (pinfunction "PA7_32") (pintype "passive"))
      (node (ref "U2") (pin "6") (pinfunction "MOSI_6") (pintype "input"))
    )
    (net (code "98") (name "Net-(U1-PA8)") (class "Default")
      (node (ref "D1") (pin "1") (pinfunction "1_1") (pintype "passive"))
      (node (ref "U1") (pin "5") (pinfunction "PA8_5") (pintype "passive"))
    )
    (net (code "99") (name "Net-(U1-PA10)") (class "Default")
      (node (ref "D3") (pin "A") (pinfunction "A_A") (pintype "passive"))
      (node (ref "U1") (pin "7") (pinfunction "PA10_7") (pintype "passive"))
    )
    (net (code "100") (name "Net-(U1-PB5)") (class "Default")
      (node (ref "S1") (pin "1") (pinfunction "1_1") (pintype "passive"))
      (node (ref "U1") (pin "13") (pinfunction "PB5_13") (pintype "passive"))
    )
    (net (code "101") (name "Net-(U1-PB6)") (class "Default")
      (node (ref "S2") (pin "1") (pinfunction "1_1") (pintype "passive"))
      (node (ref "U1") (pin "14") (pinfunction "PB6_14") (pintype "passive"))
    )
    (net (code "102") (name "Net-(U1-PB7)") (class "Default")
      (node (ref "S3") (pin "1") (pinfunction "1_1") (pintype "passive"))
      (node (ref "U1") (pin "15") (pinfunction "PB7_15") (pintype "passive"))
    )
    (net (code "103") (name "Net-(U1-PB8)") (class "Default")
      (node (ref "S4") (pin "1") (pinfunction "1_1") (pintype "passive"))
      (node (ref "U1") (pin "16") (pinfunction "PB8_16") (pintype "passive"))
    )
    (net (code "104") (name "Net-(U1-PB9)") (class "Default")
      (node (ref "S5") (pin "1") (pinfunction "1_1") (pintype "passive"))
      (node (ref "U1") (pin "17") (pinfunction "PB9_17") (pintype "passive"))
    )
    (net (code "105") (name "Net-(U1-PB10)") (class "Default")
      (node (ref "PCF1") (pin "17") (pinfunction "17_17") (pintype "passive"))
      (node (ref "U1") (pin "35") (pinfunction "PB10_35") (pintype "passive"))
    )
    (net (code "106") (name "Net-(U1-PB11)") (class "Default")
      (node (ref "PCF1") (pin "18") (pinfunction "18_18") (pintype "passive"))
      (node (ref "U1") (pin "36") (pinfunction "PB11_36") (pintype "passive"))
    )
    (net (code "107") (name "Net-(U3-A)") (class "Default")
      (node (ref "PCF1") (pin "15") (pinfunction "15_15") (pintype "passive"))
      (node (ref "U3") (pin "15") (pinfunction "A_15") (pintype "power_in"))
    )
    (net (code "108") (name "Net-(U3-DB0)") (class "Default")
      (node (ref "PCF1") (pin "7") (pinfunction "7_7") (pintype "passive"))
      (node (ref "U3") (pin "7") (pinfunction "DB0_7") (pintype "bidirectional"))
    )
    (net (code "109") (name "Net-(U3-DB1)") (class "Default")
      (node (ref "PCF1") (pin "8") (pinfunction "8_8") (pintype "passive"))
      (node (ref "U3") (pin "8") (pinfunction "DB1_8") (pintype "bidirectional"))
    )
    (net (code "110") (name "Net-(U3-DB2)") (class "Default")
      (node (ref "PCF1") (pin "9") (pinfunction "9_9") (pintype "passive"))
      (node (ref "U3") (pin "9") (pinfunction "DB2_9") (pintype "bidirectional"))
    )
    (net (code "111") (name "Net-(U3-DB3)") (class "Default")
      (node (ref "PCF1") (pin "10") (pinfunction "10_10") (pintype "passive"))
      (node (ref "U3") (pin "10") (pinfunction "DB3_10") (pintype "bidirectional"))
    )
    (net (code "112") (name "Net-(U3-DB4)") (class "Default")
      (node (ref "PCF1") (pin "11") (pinfunction "11_11") (pintype "passive"))
      (node (ref "U3") (pin "11") (pinfunction "DB4_11") (pintype "bidirectional"))
    )
    (net (code "113") (name "Net-(U3-DB5)") (class "Default")
      (node (ref "PCF1") (pin "12") (pinfunction "12_12") (pintype "passive"))
      (node (ref "U3") (pin "12") (pinfunction "DB5_12") (pintype "bidirectional"))
    )
    (net (code "114") (name "Net-(U3-DB6)") (class "Default")
      (node (ref "PCF1") (pin "13") (pinfunction "13_13") (pintype "passive"))
      (node (ref "U3") (pin "13") (pinfunction "DB6_13") (pintype "bidirectional"))
    )
    (net (code "115") (name "Net-(U3-DB7)") (class "Default")
      (node (ref "PCF1") (pin "14") (pinfunction "14_14") (pintype "passive"))
      (node (ref "U3") (pin "14") (pinfunction "DB7_14") (pintype "bidirectional"))
    )
    (net (code "116") (name "Net-(U3-E)") (class "Default")
      (node (ref "PCF1") (pin "6") (pinfunction "6_6") (pintype "passive"))
      (node (ref "U3") (pin "6") (pinfunction "E_6") (pintype "input"))
    )
    (net (code "117") (name "Net-(U3-K)") (class "Default")
      (node (ref "PCF1") (pin "16") (pinfunction "16_16") (pintype "passive"))
      (node (ref "U3") (pin "16") (pinfunction "K_16") (pintype "power_in"))
    )
    (net (code "118") (name "Net-(U3-RS)") (class "Default")
      (node (ref "PCF1") (pin "4") (pinfunction "4_4") (pintype "passive"))
      (node (ref "U3") (pin "4") (pinfunction "RS_4") (pintype "input"))
    )
    (net (code "119") (name "Net-(U3-R{slash}W)") (class "Default")
      (node (ref "PCF1") (pin "5") (pinfunction "5_5") (pintype "passive"))
      (node (ref "U3") (pin "5") (pinfunction "R/W_5") (pintype "input"))
    )
    (net (code "120") (name "Net-(U3-VDD)") (class "Default")
      (node (ref "PCF1") (pin "2") (pinfunction "2_2") (pintype "passive"))
      (node (ref "U3") (pin "2") (pinfunction "VDD_2") (pintype "power_in"))
    )
    (net (code "121") (name "Net-(U3-VO)") (class "Default")
      (node (ref "PCF1") (pin "3") (pinfunction "3_3") (pintype "passive"))
      (node (ref "U3") (pin "3") (pinfunction "VO_3") (pintype "bidirectional"))
    )
    (net (code "122") (name "Net-(U3-VSS)") (class "Default")
      (node (ref "PCF1") (pin "1") (pinfunction "1_1") (pintype "passive"))
      (node (ref "U3") (pin "1") (pinfunction "VSS_1") (pintype "power_in"))
    )
    (net (code "123") (name "Net-(U4-PA0)") (class "Default")
      (node (ref "U4") (pin "25") (pinfunction "PA0_25") (pintype "passive"))
      (node (ref "U5") (pin "8") (pinfunction "~{IRQ}_8") (pintype "input"))
    )
    (net (code "124") (name "Net-(U4-PA3)") (class "Default")
      (node (ref "U4") (pin "28") (pinfunction "PA3_28") (pintype "passive"))
      (node (ref "U5") (pin "3") (pinfunction "CE_3") (pintype "input"))
    )
    (net (code "125") (name "Net-(U4-PA4)") (class "Default")
      (node (ref "U4") (pin "29") (pinfunction "PA4_29") (pintype "passive"))
      (node (ref "U5") (pin "4") (pinfunction "~{CSN}_4") (pintype "input"))
    )
    (net (code "126") (name "Net-(U4-PA5)") (class "Default")
      (node (ref "U4") (pin "30") (pinfunction "PA5_30") (pintype "passive"))
      (node (ref "U5") (pin "5") (pinfunction "SCK_5") (pintype "input"))
    )
    (net (code "127") (name "Net-(U4-PA6)") (class "Default")
      (node (ref "U4") (pin "31") (pinfunction "PA6_31") (pintype "passive"))
      (node (ref "U5") (pin "7") (pinfunction "MISO_7") (pintype "input"))
    )
    (net (code "128") (name "Net-(U4-PA7)") (class "Default")
      (node (ref "U4") (pin "32") (pinfunction "PA7_32") (pintype "passive"))
      (node (ref "U5") (pin "6") (pinfunction "MOSI_6") (pintype "input"))
    )
    (net (code "129") (name "Net-(U4-PA8)") (class "Default")
      (node (ref "D4") (pin "1") (pinfunction "1_1") (pintype "passive"))
      (node (ref "U4") (pin "5") (pinfunction "PA8_5") (pintype "passive"))
    )
    (net (code "130") (name "Net-(U4-PA10)") (class "Default")
      (node (ref "D6") (pin "A") (pinfunction "A_A") (pintype "passive"))
      (node (ref "U4") (pin "7") (pinfunction "PA10_7") (pintype "passive"))
    )
    (net (code "131") (name "Net-(U6-PA0)") (class "Default")
      (node (ref "U6") (pin "25") (pinfunction "PA0_25") (pintype "passive"))
      (node (ref "U7") (pin "8") (pinfunction "~{IRQ}_8") (pintype "input"))
    )
    (net (code "132") (name "Net-(U6-PA3)") (class "Default")
      (node (ref "U6") (pin "28") (pinfunction "PA3_28") (pintype "passive"))
      (node (ref "U7") (pin "3") (pinfunction "CE_3") (pintype "input"))
    )
    (net (code "133") (name "Net-(U6-PA4)") (class "Default")
      (node (ref "U6") (pin "29") (pinfunction "PA4_29") (pintype "passive"))
      (node (ref "U7") (pin "4") (pinfunction "~{CSN}_4") (pintype "input"))
    )
    (net (code "134") (name "Net-(U6-PA5)") (class "Default")
      (node (ref "U6") (pin "30") (pinfunction "PA5_30") (pintype "passive"))
      (node (ref "U7") (pin "5") (pinfunction "SCK_5") (pintype "input"))
    )
    (net (code "135") (name "Net-(U6-PA6)") (class "Default")
      (node (ref "U6") (pin "31") (pinfunction "PA6_31") (pintype "passive"))
      (node (ref "U7") (pin "7") (pinfunction "MISO_7") (pintype "input"))
    )
    (net (code "136") (name "Net-(U6-PA7)") (class "Default")
      (node (ref "U6") (pin "32") (pinfunction "PA7_32") (pintype "passive"))
      (node (ref "U7") (pin "6") (pinfunction "MOSI_6") (pintype "input"))
    )
    (net (code "137") (name "Net-(U6-PA8)") (class "Default")
      (node (ref "D7") (pin "1") (pinfunction "1_1") (pintype "passive"))
      (node (ref "U6") (pin "5") (pinfunction "PA8_5") (pintype "passive"))
    )
    (net (code "138") (name "Net-(U6-PA10)") (class "Default")
      (node (ref "D9") (pin "A") (pinfunction "A_A") (pintype "passive"))
      (node (ref "U6") (pin "7") (pinfunction "PA10_7") (pintype "passive"))
    )
    (net (code "139") (name "Net-(U8-PA0)") (class "Default")
      (node (ref "U8") (pin "25") (pinfunction "PA0_25") (pintype "passive"))
      (node (ref "U9") (pin "8") (pinfunction "~{IRQ}_8") (pintype "input"))
    )
    (net (code "140") (name "Net-(U8-PA3)") (class "Default")
      (node (ref "U8") (pin "28") (pinfunction "PA3_28") (pintype "passive"))
      (node (ref "U9") (pin "3") (pinfunction "CE_3") (pintype "input"))
    )
    (net (code "141") (name "Net-(U8-PA4)") (class "Default")
      (node (ref "U8") (pin "29") (pinfunction "PA4_29") (pintype "passive"))
      (node (ref "U9") (pin "4") (pinfunction "~{CSN}_4") (pintype "input"))
    )
    (net (code "142") (name "Net-(U8-PA5)") (class "Default")
      (node (ref "U8") (pin "30") (pinfunction "PA5_30") (pintype "passive"))
      (node (ref "U9") (pin "5") (pinfunction "SCK_5") (pintype "input"))
    )
    (net (code "143") (name "Net-(U8-PA6)") (class "Default")
      (node (ref "U8") (pin "31") (pinfunction "PA6_31") (pintype "passive"))
      (node (ref "U9") (pin "7") (pinfunction "MISO_7") (pintype "input"))
    )
    (net (code "144") (name "Net-(U8-PA7)") (class "Default")
      (node (ref "U8") (pin "32") (pinfunction "PA7_32") (pintype "passive"))
      (node (ref "U9") (pin "6") (pinfunction "MOSI_6") (pintype "input"))
    )
    (net (code "145") (name "Net-(U8-PA8)") (class "Default")
      (node (ref "D10") (pin "1") (pinfunction "1_1") (pintype "passive"))
      (node (ref "U8") (pin "5") (pinfunction "PA8_5") (pintype "passive"))
    )
    (net (code "146") (name "Net-(U8-PA10)") (class "Default")
      (node (ref "D12") (pin "A") (pinfunction "A_A") (pintype "passive"))
      (node (ref "U8") (pin "7") (pinfunction "PA10_7") (pintype "passive"))
    )
    (net (code "147") (name "unconnected-(IC1-~{MR}-Pad10)") (class "Default")
      (node (ref "IC1") (pin "10") (pinfunction "~{MR}_10") (pintype "bidirectional"))
    )
    (net (code "148") (name "unconnected-(IC2-Q7S-Pad9)") (class "Default")
      (node (ref "IC2") (pin "9") (pinfunction "Q7S_9") (pintype "bidirectional"))
    )
    (net (code "149") (name "unconnected-(IC2-~{MR}-Pad10)") (class "Default")
      (node (ref "IC2") (pin "10") (pinfunction "~{MR}_10") (pintype "bidirectional"))
    )
    (net (code "150") (name "unconnected-(IC3-~{MR}-Pad10)") (class "Default")
      (node (ref "IC3") (pin "10") (pinfunction "~{MR}_10") (pintype "bidirectional"))
    )
    (net (code "151") (name "unconnected-(IC4-Q7S-Pad9)") (class "Default")
      (node (ref "IC4") (pin "9") (pinfunction "Q7S_9") (pintype "bidirectional"))
    )
    (net (code "152") (name "unconnected-(IC4-~{MR}-Pad10)") (class "Default")
      (node (ref "IC4") (pin "10") (pinfunction "~{MR}_10") (pintype "bidirectional"))
    )
    (net (code "153") (name "unconnected-(IC5-~{MR}-Pad10)") (class "Default")
      (node (ref "IC5") (pin "10") (pinfunction "~{MR}_10") (pintype "bidirectional"))
    )
    (net (code "154") (name "unconnected-(IC6-Q7S-Pad9)") (class "Default")
      (node (ref "IC6") (pin "9") (pinfunction "Q7S_9") (pintype "bidirectional"))
    )
    (net (code "155") (name "unconnected-(IC6-~{MR}-Pad10)") (class "Default")
      (node (ref "IC6") (pin "10") (pinfunction "~{MR}_10") (pintype "bidirectional"))
    )
    (net (code "156") (name "unconnected-(IC7-~{MR}-Pad10)") (class "Default")
      (node (ref "IC7") (pin "10") (pinfunction "~{MR}_10") (pintype "bidirectional"))
    )
    (net (code "157") (name "unconnected-(IC8-Q7S-Pad9)") (class "Default")
      (node (ref "IC8") (pin "9") (pinfunction "Q7S_9") (pintype "bidirectional"))
    )
    (net (code "158") (name "unconnected-(IC8-~{MR}-Pad10)") (class "Default")
      (node (ref "IC8") (pin "10") (pinfunction "~{MR}_10") (pintype "bidirectional"))
    )
    (net (code "159") (name "unconnected-(S1-Pad2)") (class "Default")
      (node (ref "S1") (pin "2") (pinfunction "2_2") (pintype "passive"))
    )
    (net (code "160") (name "unconnected-(S1-Pad4)") (class "Default")
      (node (ref "S1") (pin "4") (pinfunction "4_4") (pintype "passive"))
    )
    (net (code "161") (name "unconnected-(S2-Pad2)") (class "Default")
      (node (ref "S2") (pin "2") (pinfunction "2_2") (pintype "passive"))
    )
    (net (code "162") (name "unconnected-(S2-Pad4)") (class "Default")
      (node (ref "S2") (pin "4") (pinfunction "4_4") (pintype "passive"))
    )
    (net (code "163") (name "unconnected-(S3-Pad2)") (class "Default")
      (node (ref "S3") (pin "2") (pinfunction "2_2") (pintype "passive"))
    )
    (net (code "164") (name "unconnected-(S3-Pad4)") (class "Default")
      (node (ref "S3") (pin "4") (pinfunction "4_4") (pintype "passive"))
    )
    (net (code "165") (name "unconnected-(S4-Pad2)") (class "Default")
      (node (ref "S4") (pin "2") (pinfunction "2_2") (pintype "passive"))
    )
    (net (code "166") (name "unconnected-(S4-Pad4)") (class "Default")
      (node (ref "S4") (pin "4") (pinfunction "4_4") (pintype "passive"))
    )
    (net (code "167") (name "unconnected-(S5-Pad2)") (class "Default")
      (node (ref "S5") (pin "2") (pinfunction "2_2") (pintype "passive"))
    )
    (net (code "168") (name "unconnected-(S5-Pad4)") (class "Default")
      (node (ref "S5") (pin "4") (pinfunction "4_4") (pintype "passive"))
    )
    (net (code "169") (name "unconnected-(S6-Pad2)") (class "Default")
      (node (ref "S6") (pin "2") (pinfunction "2_2") (pintype "passive"))
    )
    (net (code "170") (name "unconnected-(S6-Pad4)") (class "Default")
      (node (ref "S6") (pin "4") (pinfunction "4_4") (pintype "passive"))
    )
    (net (code "171") (name "unconnected-(S7-Pad2)") (class "Default")
      (node (ref "S7") (pin "2") (pinfunction "2_2") (pintype "passive"))
    )
    (net (code "172") (name "unconnected-(S7-Pad4)") (class "Default")
      (node (ref "S7") (pin "4") (pinfunction "4_4") (pintype "passive"))
    )
    (net (code "173") (name "unconnected-(S8-Pad2)") (class "Default")
      (node (ref "S8") (pin "2") (pinfunction "2_2") (pintype "passive"))
    )
    (net (code "174") (name "unconnected-(S8-Pad4)") (class "Default")
      (node (ref "S8") (pin "4") (pinfunction "4_4") (pintype "passive"))
    )
    (net (code "175") (name "unconnected-(S9-Pad2)") (class "Default")
      (node (ref "S9") (pin "2") (pinfunction "2_2") (pintype "passive"))
    )
    (net (code "176") (name "unconnected-(S9-Pad4)") (class "Default")
      (node (ref "S9") (pin "4") (pinfunction "4_4") (pintype "passive"))
    )
    (net (code "177") (name "unconnected-(U1-3V3-Pad20)") (class "Default")
      (node (ref "U1") (pin "20") (pinfunction "3V3_20") (pintype "passive"))
    )
    (net (code "178") (name "unconnected-(U1-3V3-Pad38)") (class "Default")
      (node (ref "U1") (pin "38") (pinfunction "3V3_38") (pintype "passive"))
    )
    (net (code "179") (name "unconnected-(U1-GND-Pad19)") (class "Default")
      (node (ref "U1") (pin "19") (pinfunction "GND_19") (pintype "passive"))
    )
    (net (code "180") (name "unconnected-(U1-PA1-Pad26)") (class "Default")
      (node (ref "U1") (pin "26") (pinfunction "PA1_26") (pintype "passive"))
    )
    (net (code "181") (name "unconnected-(U1-PA2-Pad27)") (class "Default")
      (node (ref "U1") (pin "27") (pinfunction "PA2_27") (pintype "passive"))
    )
    (net (code "182") (name "unconnected-(U1-PA11-Pad8)") (class "Default")
      (node (ref "U1") (pin "8") (pinfunction "PA11_8") (pintype "passive"))
    )
    (net (code "183") (name "unconnected-(U1-PA12-Pad9)") (class "Default")
      (node (ref "U1") (pin "9") (pinfunction "PA12_9") (pintype "passive"))
    )
    (net (code "184") (name "unconnected-(U1-PA15-Pad10)") (class "Default")
      (node (ref "U1") (pin "10") (pinfunction "PA15_10") (pintype "passive"))
    )
    (net (code "185") (name "unconnected-(U1-PB0-Pad33)") (class "Default")
      (node (ref "U1") (pin "33") (pinfunction "PB0_33") (pintype "passive"))
    )
    (net (code "186") (name "unconnected-(U1-PB1-Pad34)") (class "Default")
      (node (ref "U1") (pin "34") (pinfunction "PB1_34") (pintype "passive"))
    )
    (net (code "187") (name "unconnected-(U1-PB3-Pad11)") (class "Default")
      (node (ref "U1") (pin "11") (pinfunction "PB3_11") (pintype "passive"))
    )
    (net (code "188") (name "unconnected-(U1-PB4-Pad12)") (class "Default")
      (node (ref "U1") (pin "12") (pinfunction "PB4_12") (pintype "passive"))
    )
    (net (code "189") (name "unconnected-(U1-PB14-Pad3)") (class "Default")
      (node (ref "U1") (pin "3") (pinfunction "PB14_3") (pintype "passive"))
    )
    (net (code "190") (name "unconnected-(U1-PC13-Pad22)") (class "Default")
      (node (ref "U1") (pin "22") (pinfunction "PC13_22") (pintype "passive"))
    )
    (net (code "191") (name "unconnected-(U1-PC14-Pad23)") (class "Default")
      (node (ref "U1") (pin "23") (pinfunction "PC14_23") (pintype "passive"))
    )
    (net (code "192") (name "unconnected-(U1-PC15-Pad24)") (class "Default")
      (node (ref "U1") (pin "24") (pinfunction "PC15_24") (pintype "passive"))
    )
    (net (code "193") (name "unconnected-(U1-VBAT-Pad21)") (class "Default")
      (node (ref "U1") (pin "21") (pinfunction "VBAT_21") (pintype "passive"))
    )
    (net (code "194") (name "unconnected-(U4-3V3-Pad20)") (class "Default")
      (node (ref "U4") (pin "20") (pinfunction "3V3_20") (pintype "passive"))
    )
    (net (code "195") (name "unconnected-(U4-3V3-Pad38)") (class "Default")
      (node (ref "U4") (pin "38") (pinfunction "3V3_38") (pintype "passive"))
    )
    (net (code "196") (name "unconnected-(U4-GND-Pad19)") (class "Default")
      (node (ref "U4") (pin "19") (pinfunction "GND_19") (pintype "passive"))
    )
    (net (code "197") (name "unconnected-(U4-PA1-Pad26)") (class "Default")
      (node (ref "U4") (pin "26") (pinfunction "PA1_26") (pintype "passive"))
    )
    (net (code "198") (name "unconnected-(U4-PA2-Pad27)") (class "Default")
      (node (ref "U4") (pin "27") (pinfunction "PA2_27") (pintype "passive"))
    )
    (net (code "199") (name "unconnected-(U4-PA11-Pad8)") (class "Default")
      (node (ref "U4") (pin "8") (pinfunction "PA11_8") (pintype "passive"))
    )
    (net (code "200") (name "unconnected-(U4-PA12-Pad9)") (class "Default")
      (node (ref "U4") (pin "9") (pinfunction "PA12_9") (pintype "passive"))
    )
    (net (code "201") (name "unconnected-(U4-PA15-Pad10)") (class "Default")
      (node (ref "U4") (pin "10") (pinfunction "PA15_10") (pintype "passive"))
    )
    (net (code "202") (name "unconnected-(U4-PB0-Pad33)") (class "Default")
      (node (ref "U4") (pin "33") (pinfunction "PB0_33") (pintype "passive"))
    )
    (net (code "203") (name "unconnected-(U4-PB1-Pad34)") (class "Default")
      (node (ref "U4") (pin "34") (pinfunction "PB1_34") (pintype "passive"))
    )
    (net (code "204") (name "unconnected-(U4-PB3-Pad11)") (class "Default")
      (node (ref "U4") (pin "11") (pinfunction "PB3_11") (pintype "passive"))
    )
    (net (code "205") (name "unconnected-(U4-PB4-Pad12)") (class "Default")
      (node (ref "U4") (pin "12") (pinfunction "PB4_12") (pintype "passive"))
    )
    (net (code "206") (name "unconnected-(U4-PB5-Pad13)") (class "Default")
      (node (ref "U4") (pin "13") (pinfunction "PB5_13") (pintype "passive"))
    )
    (net (code "207") (name "unconnected-(U4-PB6-Pad14)") (class "Default")
      (node (ref "U4") (pin "14") (pinfunction "PB6_14") (pintype "passive"))
    )
    (net (code "208") (name "unconnected-(U4-PB7-Pad15)") (class "Default")
      (node (ref "U4") (pin "15") (pinfunction "PB7_15") (pintype "passive"))
    )
    (net (code "209") (name "unconnected-(U4-PB8-Pad16)") (class "Default")
      (node (ref "U4") (pin "16") (pinfunction "PB8_16") (pintype "passive"))
    )
    (net (code "210") (name "unconnected-(U4-PB9-Pad17)") (class "Default")
      (node (ref "U4") (pin "17") (pinfunction "PB9_17") (pintype "passive"))
    )
    (net (code "211") (name "unconnected-(U4-PB10-Pad35)") (class "Default")
      (node (ref "U4") (pin "35") (pinfunction "PB10_35") (pintype "passive"))
    )
    (net (code "212") (name "unconnected-(U4-PB11-Pad36)") (class "Default")
      (node (ref "U4") (pin "36") (pinfunction "PB11_36") (pintype "passive"))
    )
    (net (code "213") (name "unconnected-(U4-PB14-Pad3)") (class "Default")
      (node (ref "U4") (pin "3") (pinfunction "PB14_3") (pintype "passive"))
    )
    (net (code "214") (name "unconnected-(U4-PC13-Pad22)") (class "Default")
      (node (ref "U4") (pin "22") (pinfunction "PC13_22") (pintype "passive"))
    )
    (net (code "215") (name "unconnected-(U4-PC14-Pad23)") (class "Default")
      (node (ref "U4") (pin "23") (pinfunction "PC14_23") (pintype "passive"))
    )
    (net (code "216") (name "unconnected-(U4-PC15-Pad24)") (class "Default")
      (node (ref "U4") (pin "24") (pinfunction "PC15_24") (pintype "passive"))
    )
    (net (code "217") (name "unconnected-(U4-VBAT-Pad21)") (class "Default")
      (node (ref "U4") (pin "21") (pinfunction "VBAT_21") (pintype "passive"))
    )
    (net (code "218") (name "unconnected-(U6-3V3-Pad20)") (class "Default")
      (node (ref "U6") (pin "20") (pinfunction "3V3_20") (pintype "passive"))
    )
    (net (code "219") (name "unconnected-(U6-3V3-Pad38)") (class "Default")
      (node (ref "U6") (pin "38") (pinfunction "3V3_38") (pintype "passive"))
    )
    (net (code "220") (name "unconnected-(U6-GND-Pad19)") (class "Default")
      (node (ref "U6") (pin "19") (pinfunction "GND_19") (pintype "passive"))
    )
    (net (code "221") (name "unconnected-(U6-PA1-Pad26)") (class "Default")
      (node (ref "U6") (pin "26") (pinfunction "PA1_26") (pintype "passive"))
    )
    (net (code "222") (name "unconnected-(U6-PA2-Pad27)") (class "Default")
      (node (ref "U6") (pin "27") (pinfunction "PA2_27") (pintype "passive"))
    )
    (net (code "223") (name "unconnected-(U6-PA11-Pad8)") (class "Default")
      (node (ref "U6") (pin "8") (pinfunction "PA11_8") (pintype "passive"))
    )
    (net (code "224") (name "unconnected-(U6-PA12-Pad9)") (class "Default")
      (node (ref "U6") (pin "9") (pinfunction "PA12_9") (pintype "passive"))
    )
    (net (code "225") (name "unconnected-(U6-PA15-Pad10)") (class "Default")
      (node (ref "U6") (pin "10") (pinfunction "PA15_10") (pintype "passive"))
    )
    (net (code "226") (name "unconnected-(U6-PB0-Pad33)") (class "Default")
      (node (ref "U6") (pin "33") (pinfunction "PB0_33") (pintype "passive"))
    )
    (net (code "227") (name "unconnected-(U6-PB1-Pad34)") (class "Default")
      (node (ref "U6") (pin "34") (pinfunction "PB1_34") (pintype "passive"))
    )
    (net (code "228") (name "unconnected-(U6-PB3-Pad11)") (class "Default")
      (node (ref "U6") (pin "11") (pinfunction "PB3_11") (pintype "passive"))
    )
    (net (code "229") (name "unconnected-(U6-PB4-Pad12)") (class "Default")
      (node (ref "U6") (pin "12") (pinfunction "PB4_12") (pintype "passive"))
    )
    (net (code "230") (name "unconnected-(U6-PB5-Pad13)") (class "Default")
      (node (ref "U6") (pin "13") (pinfunction "PB5_13") (pintype "passive"))
    )
    (net (code "231") (name "unconnected-(U6-PB6-Pad14)") (class "Default")
      (node (ref "U6") (pin "14") (pinfunction "PB6_14") (pintype "passive"))
    )
    (net (code "232") (name "unconnected-(U6-PB7-Pad15)") (class "Default")
      (node (ref "U6") (pin "15") (pinfunction "PB7_15") (pintype "passive"))
    )
    (net (code "233") (name "unconnected-(U6-PB8-Pad16)") (class "Default")
      (node (ref "U6") (pin "16") (pinfunction "PB8_16") (pintype "passive"))
    )
    (net (code "234") (name "unconnected-(U6-PB9-Pad17)") (class "Default")
      (node (ref "U6") (pin "17") (pinfunction "PB9_17") (pintype "passive"))
    )
    (net (code "235") (name "unconnected-(U6-PB10-Pad35)") (class "Default")
      (node (ref "U6") (pin "35") (pinfunction "PB10_35") (pintype "passive"))
    )
    (net (code "236") (name "unconnected-(U6-PB11-Pad36)") (class "Default")
      (node (ref "U6") (pin "36") (pinfunction "PB11_36") (pintype "passive"))
    )
    (net (code "237") (name "unconnected-(U6-PB14-Pad3)") (class "Default")
      (node (ref "U6") (pin "3") (pinfunction "PB14_3") (pintype "passive"))
    )
    (net (code "238") (name "unconnected-(U6-PC13-Pad22)") (class "Default")
      (node (ref "U6") (pin "22") (pinfunction "PC13_22") (pintype "passive"))
    )
    (net (code "239") (name "unconnected-(U6-PC14-Pad23)") (class "Default")
      (node (ref "U6") (pin "23") (pinfunction "PC14_23") (pintype "passive"))
    )
    (net (code "240") (name "unconnected-(U6-PC15-Pad24)") (class "Default")
      (node (ref "U6") (pin "24") (pinfunction "PC15_24") (pintype "passive"))
    )
    (net (code "241") (name "unconnected-(U6-VBAT-Pad21)") (class "Default")
      (node (ref "U6") (pin "21") (pinfunction "VBAT_21") (pintype "passive"))
    )
    (net (code "242") (name "unconnected-(U8-3V3-Pad20)") (class "Default")
      (node (ref "U8") (pin "20") (pinfunction "3V3_20") (pintype "passive"))
    )
    (net (code "243") (name "unconnected-(U8-3V3-Pad38)") (class "Default")
      (node (ref "U8") (pin "38") (pinfunction "3V3_38") (pintype "passive"))
    )
    (net (code "244") (name "unconnected-(U8-GND-Pad19)") (class "Default")
      (node (ref "U8") (pin "19") (pinfunction "GND_19") (pintype "passive"))
    )
    (net (code "245") (name "unconnected-(U8-PA1-Pad26)") (class "Default")
      (node (ref "U8") (pin "26") (pinfunction "PA1_26") (pintype "passive"))
    )
    (net (code "246") (name "unconnected-(U8-PA2-Pad27)") (class "Default")
      (node (ref "U8") (pin "27") (pinfunction "PA2_27") (pintype "passive"))
    )
    (net (code "247") (name "unconnected-(U8-PA11-Pad8)") (class "Default")
      (node (ref "U8") (pin "8") (pinfunction "PA11_8") (pintype "passive"))
    )
    (net (code "248") (name "unconnected-(U8-PA12-Pad9)") (class "Default")
      (node (ref "U8") (pin "9") (pinfunction "PA12_9") (pintype "passive"))
    )
    (net (code "249") (name "unconnected-(U8-PA15-Pad10)") (class "Default")
      (node (ref "U8") (pin "10") (pinfunction "PA15_10") (pintype "passive"))
    )
    (net (code "250") (name "unconnected-(U8-PB0-Pad33)") (class "Default")
      (node (ref "U8") (pin "33") (pinfunction "PB0_33") (pintype "passive"))
    )
    (net (code "251") (name "unconnected-(U8-PB1-Pad34)") (class "Default")
      (node (ref "U8") (pin "34") (pinfunction "PB1_34") (pintype "passive"))
    )
    (net (code "252") (name "unconnected-(U8-PB3-Pad11)") (class "Default")
      (node (ref "U8") (pin "11") (pinfunction "PB3_11") (pintype "passive"))
    )
    (net (code "253") (name "unconnected-(U8-PB4-Pad12)") (class "Default")
      (node (ref "U8") (pin "12") (pinfunction "PB4_12") (pintype "passive"))
    )
    (net (code "254") (name "unconnected-(U8-PB5-Pad13)") (class "Default")
      (node (ref "U8") (pin "13") (pinfunction "PB5_13") (pintype "passive"))
    )
    (net (code "255") (name "unconnected-(U8-PB6-Pad14)") (class "Default")
      (node (ref "U8") (pin "14") (pinfunction "PB6_14") (pintype "passive"))
    )
    (net (code "256") (name "unconnected-(U8-PB7-Pad15)") (class "Default")
      (node (ref "U8") (pin "15") (pinfunction "PB7_15") (pintype "passive"))
    )
    (net (code "257") (name "unconnected-(U8-PB8-Pad16)") (class "Default")
      (node (ref "U8") (pin "16") (pinfunction "PB8_16") (pintype "passive"))
    )
    (net (code "258") (name "unconnected-(U8-PB9-Pad17)") (class "Default")
      (node (ref "U8") (pin "17") (pinfunction "PB9_17") (pintype "passive"))
    )
    (net (code "259") (name "unconnected-(U8-PB10-Pad35)") (class "Default")
      (node (ref "U8") (pin "35") (pinfunction "PB10_35") (pintype "passive"))
    )
    (net (code "260") (name "unconnected-(U8-PB11-Pad36)") (class "Default")
      (node (ref "U8") (pin "36") (pinfunction "PB11_36") (pintype "passive"))
    )
    (net (code "261") (name "unconnected-(U8-PB14-Pad3)") (class "Default")
      (node (ref "U8") (pin "3") (pinfunction "PB14_3") (pintype "passive"))
    )
    (net (code "262") (name "unconnected-(U8-PC13-Pad22)") (class "Default")
      (node (ref "U8") (pin "22") (pinfunction "PC13_22") (pintype "passive"))
    )
    (net (code "263") (name "unconnected-(U8-PC14-Pad23)") (class "Default")
      (node (ref "U8") (pin "23") (pinfunction "PC14_23") (pintype "passive"))
    )
    (net (code "264") (name "unconnected-(U8-PC15-Pad24)") (class "Default")
      (node (ref "U8") (pin "24") (pinfunction "PC15_24") (pintype "passive"))
    )
    (net (code "265") (name "unconnected-(U8-VBAT-Pad21)") (class "Default")
      (node (ref "U8") (pin "21") (pinfunction "VBAT_21") (pintype "passive"))
    )
  )
)
